# MAIN.net
KiCad netlist of a schematic drawn in Altium Designer
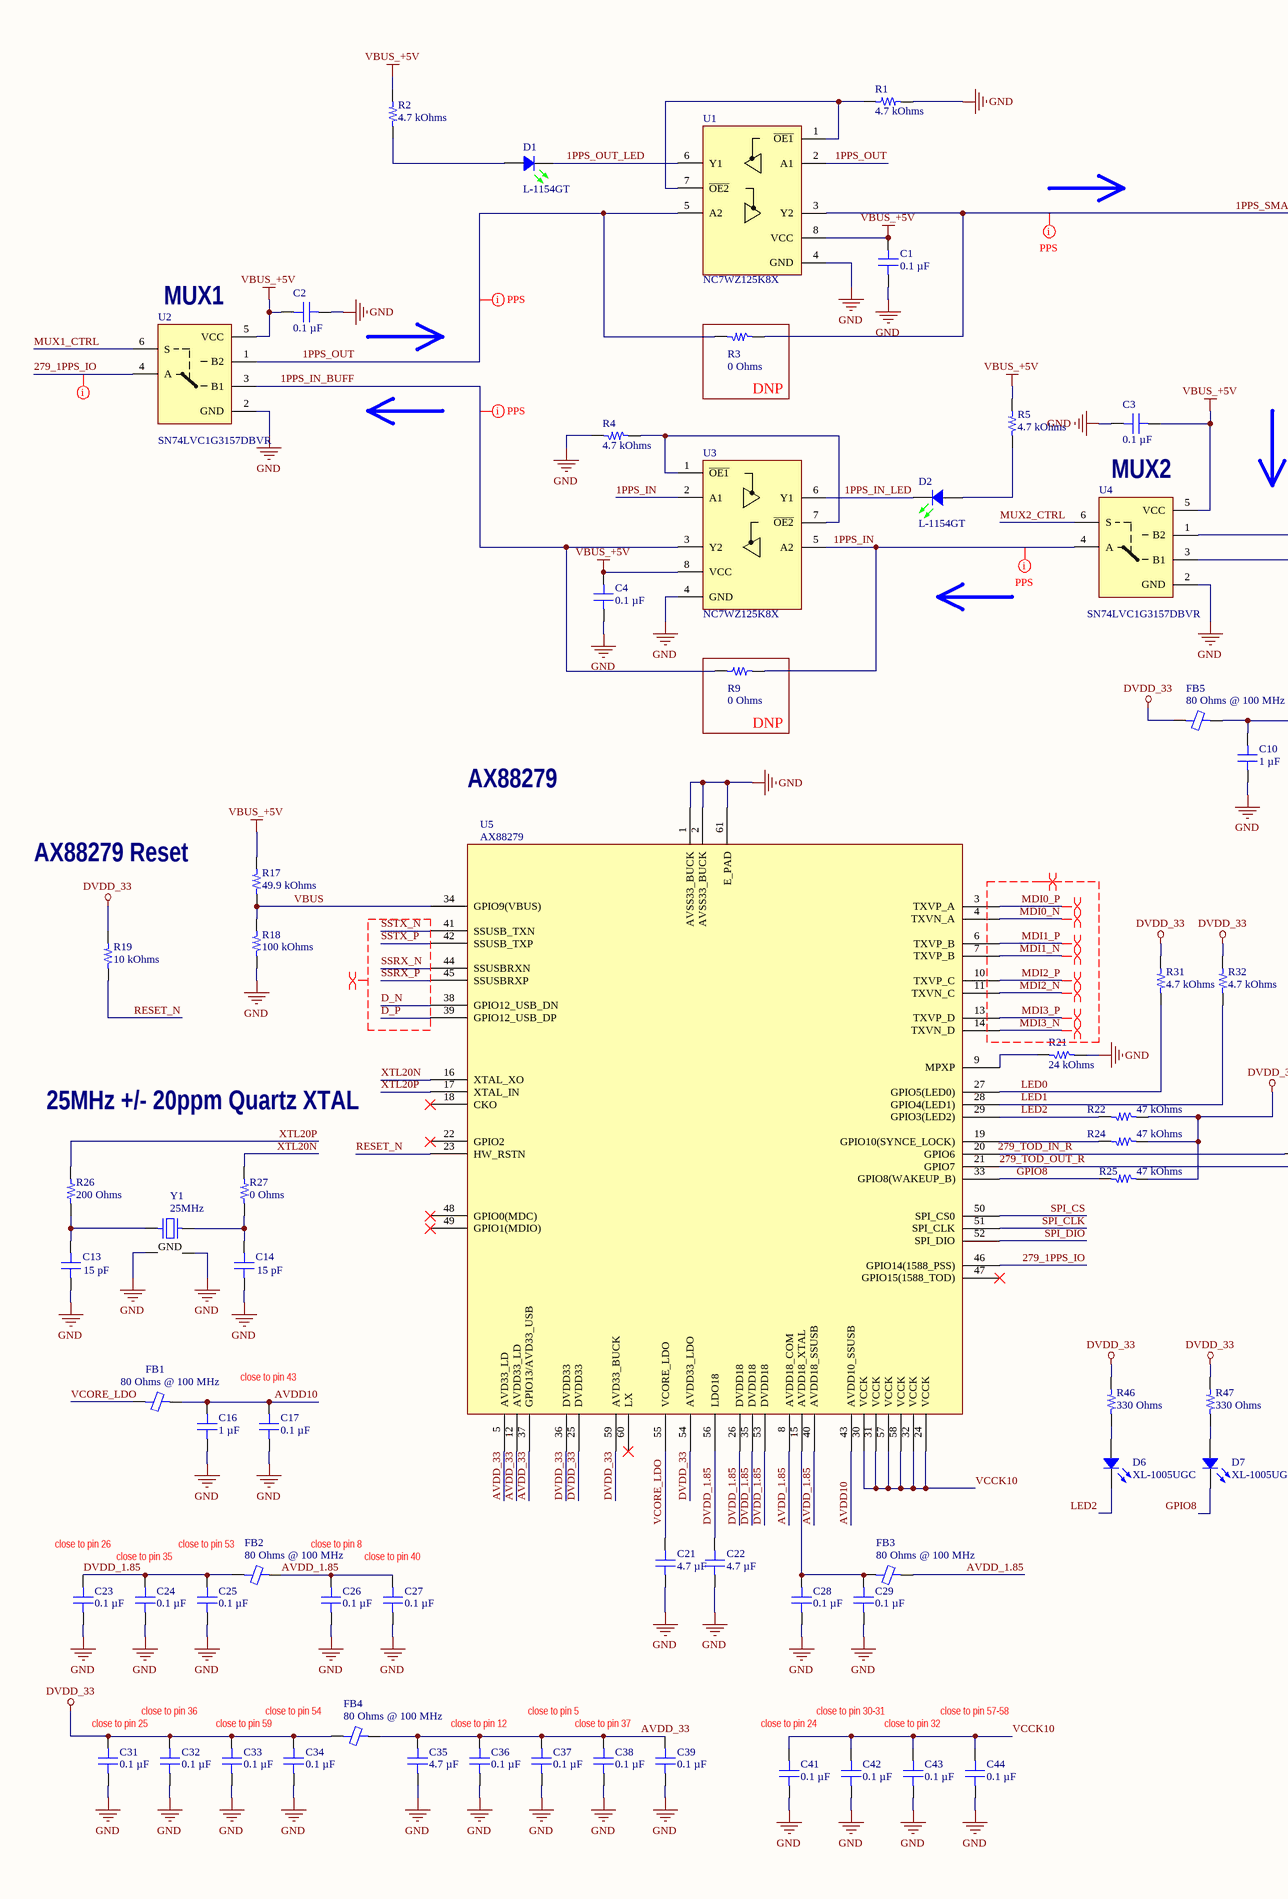
[diagram p0: MAIN.SchDoc, left]
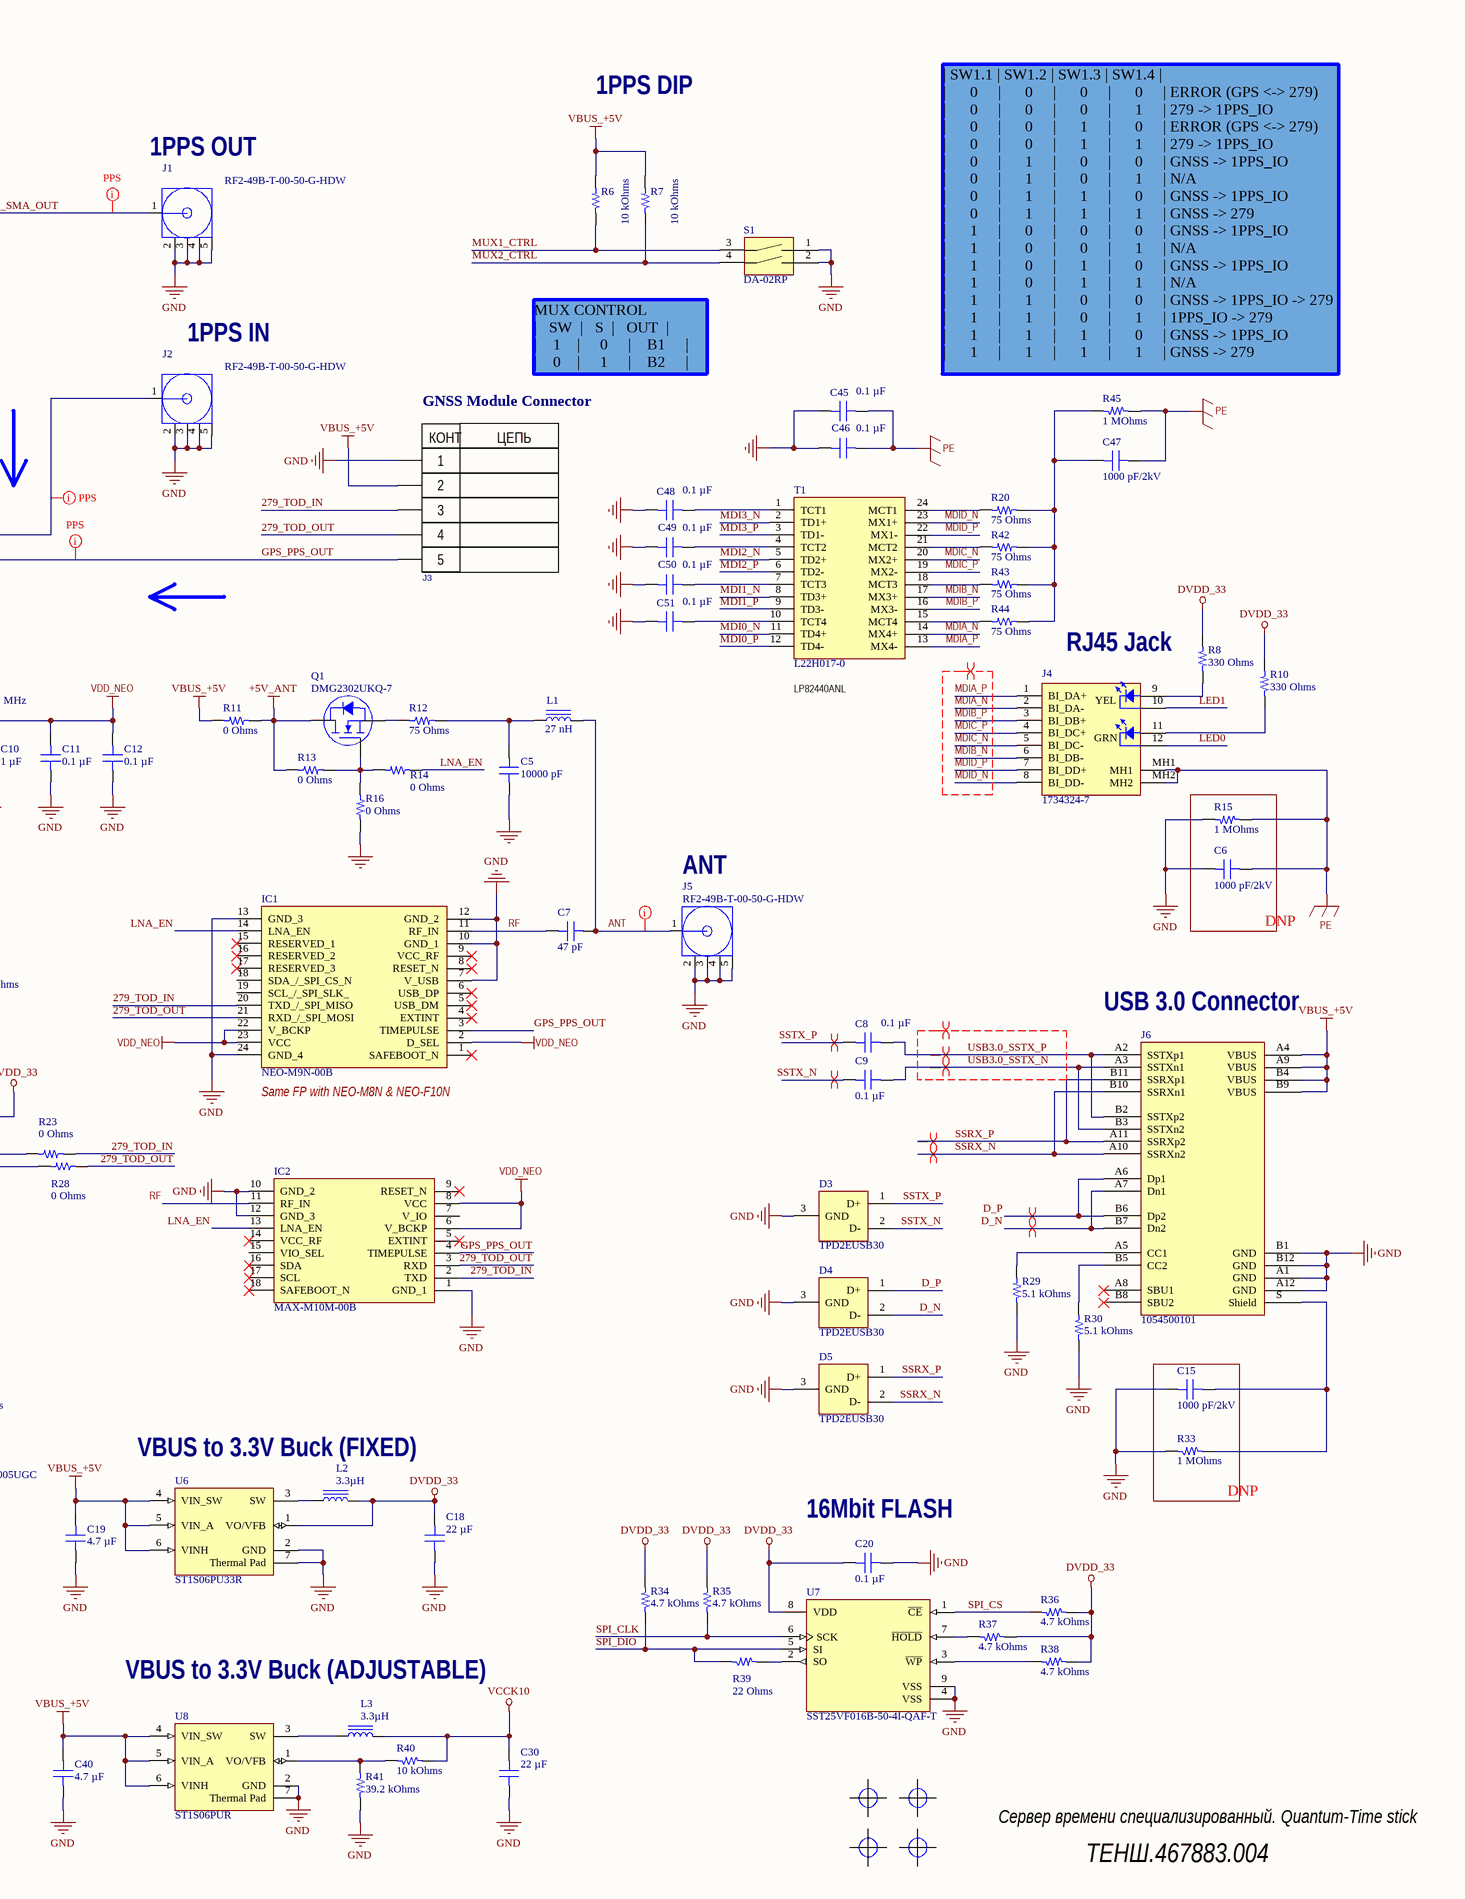
[diagram p1: MAIN.SchDoc, right]

(export (version "E")
  (design (tool "Eeschema 10.0.6"))
  (components
    (comp (ref "C1")
      (value "0.1 µF")
      (footprint "CAP 0402_1005")
      (description "CAP CER 0.1UF 10V X7R 0402")
      (fields (field (name "TOLERANCE") "±10%") (field (name "MANUFACTURER") "Yageo"))
      (libsource (lib "Celestial Altium Library - altium_library") (part "Capacitor"))
    )
    (comp (ref "C2")
      (value "0.1 µF")
      (footprint "CAP 0402_1005")
      (description "CAP CER 0.1UF 10V X7R 0402")
      (fields (field (name "TOLERANCE") "±10%") (field (name "MANUFACTURER") "Yageo"))
      (libsource (lib "Celestial Altium Library - altium_library") (part "Capacitor"))
    )
    (comp (ref "C3")
      (value "0.1 µF")
      (footprint "CAP 0402_1005")
      (description "CAP CER 0.1UF 10V X7R 0402")
      (fields (field (name "TOLERANCE") "±10%") (field (name "MANUFACTURER") "Yageo"))
      (libsource (lib "Celestial Altium Library - altium_library") (part "Capacitor"))
    )
    (comp (ref "C4")
      (value "0.1 µF")
      (footprint "CAP 0402_1005")
      (description "CAP CER 0.1UF 10V X7R 0402")
      (fields (field (name "TOLERANCE") "±10%") (field (name "MANUFACTURER") "Yageo"))
      (libsource (lib "Celestial Altium Library - altium_library") (part "Capacitor"))
    )
    (comp (ref "C5")
      (value "10000 pF")
      (footprint "CAP 0402_1005")
      (description "CAP CER 10000PF 50V X7R 0402")
      (fields (field (name "PART NUMBER") "CC0402KRX7R9BB103") (field (name "MANUFACTURER") "Yageo"))
      (libsource (lib "Celestial Altium Library - altium_library") (part "Capacitor"))
    )
    (comp (ref "C6")
      (value "1000 pF/2kV")
      (footprint "CAP 1206_3216 - 0.8MM")
      (description "CAP CER 1000PF 2KV X7R 1206")
      (fields (field (name "PART NUMBER") "CC1206KKX7RDBB102") (field (name "MANUFACTURER") "Yageo"))
      (libsource (lib "Celestial Altium Library - altium_library") (part "Capacitor"))
    )
    (comp (ref "C7")
      (value "47 pF")
      (footprint "CAP 0402_1005")
      (description "CAP CER 47PF 50V C0G/NPO 0402")
      (fields (field (name "MANUFACTURER") "Yageo") (field (name "TOLERANCE") "±10%"))
      (libsource (lib "Celestial Altium Library - altium_library") (part "Capacitor"))
    )
    (comp (ref "C8")
      (value "0.1 µF")
      (footprint "CAP 0402_1005")
      (description "CAP CER 0.1UF 10V X7R 0402")
      (fields (field (name "TOLERANCE") "±10%") (field (name "MANUFACTURER") "Yageo"))
      (libsource (lib "Celestial Altium Library - altium_library") (part "Capacitor"))
    )
    (comp (ref "C9")
      (value "0.1 µF")
      (footprint "CAP 0402_1005")
      (description "CAP CER 0.1UF 10V X7R 0402")
      (fields (field (name "TOLERANCE") "±10%") (field (name "MANUFACTURER") "Yageo"))
      (libsource (lib "Celestial Altium Library - altium_library") (part "Capacitor"))
    )
    (comp (ref "C10")
      (value "1 µF")
      (footprint "CAP 0402_1005")
      (description "CAP CER 1UF 10V X5R 0402")
      (fields (field (name "TOLERANCE") "±10%") (field (name "MANUFACTURER") "Yageo"))
      (libsource (lib "Celestial Altium Library - altium_library") (part "Capacitor"))
    )
    (comp (ref "C11")
      (value "0.1 µF")
      (footprint "CAP 0402_1005")
      (description "CAP CER 0.1UF 10V X7R 0402")
      (fields (field (name "TOLERANCE") "±10%") (field (name "MANUFACTURER") "Yageo"))
      (libsource (lib "Celestial Altium Library - altium_library") (part "Capacitor"))
    )
    (comp (ref "C12")
      (value "0.1 µF")
      (footprint "CAP 0402_1005")
      (description "CAP CER 0.1UF 10V X7R 0402")
      (fields (field (name "TOLERANCE") "±10%") (field (name "MANUFACTURER") "Yageo"))
      (libsource (lib "Celestial Altium Library - altium_library") (part "Capacitor"))
    )
    (comp (ref "C13")
      (value "15 pF")
      (footprint "CAP 0402_1005")
      (description "CAP CER 15PF 50V C0G/NPO 0402")
      (fields (field (name "MANUFACTURER") "Yageo") (field (name "TOLERANCE") "±10%"))
      (libsource (lib "Celestial Altium Library - altium_library") (part "Capacitor"))
    )
    (comp (ref "C14")
      (value "15 pF")
      (footprint "CAP 0402_1005")
      (description "CAP CER 15PF 50V C0G/NPO 0402")
      (fields (field (name "MANUFACTURER") "Yageo") (field (name "TOLERANCE") "±10%"))
      (libsource (lib "Celestial Altium Library - altium_library") (part "Capacitor"))
    )
    (comp (ref "C15")
      (value "1000 pF/2kV")
      (footprint "CAP 1206_3216 - 0.8MM")
      (description "CAP CER 1000PF 2KV X7R 1206")
      (fields (field (name "PART NUMBER") "CC1206KKX7RDBB102") (field (name "MANUFACTURER") "Yageo"))
      (libsource (lib "Celestial Altium Library - altium_library") (part "Capacitor"))
    )
    (comp (ref "C16")
      (value "1 µF")
      (footprint "CAP 0402_1005")
      (description "CAP CER 1UF 10V X5R 0402")
      (fields (field (name "TOLERANCE") "±10%") (field (name "MANUFACTURER") "Yageo"))
      (libsource (lib "Celestial Altium Library - altium_library") (part "Capacitor"))
    )
    (comp (ref "C17")
      (value "0.1 µF")
      (footprint "CAP 0402_1005")
      (description "CAP CER 0.1UF 10V X7R 0402")
      (fields (field (name "TOLERANCE") "±10%") (field (name "MANUFACTURER") "Yageo"))
      (libsource (lib "Celestial Altium Library - altium_library") (part "Capacitor"))
    )
    (comp (ref "C18")
      (value "22 µF")
      (footprint "CAP 0603_1608")
      (description "CAP CER 22UF 10V X5R 0603")
      (fields (field (name "MANUFACTURER") "Yageo") (field (name "TOLERANCE") "±20%"))
      (libsource (lib "Celestial Altium Library - altium_library") (part "Capacitor"))
    )
    (comp (ref "C19")
      (value "4.7 µF")
      (footprint "CAP 0402_1005")
      (description "CAP CER 4.7UF 10V X5R 0402")
      (fields (field (name "TOLERANCE") "±20%") (field (name "MANUFACTURER") "Yageo"))
      (libsource (lib "Celestial Altium Library - altium_library") (part "Capacitor"))
    )
    (comp (ref "C20")
      (value "0.1 µF")
      (footprint "CAP 0402_1005")
      (description "CAP CER 0.1UF 10V X7R 0402")
      (fields (field (name "TOLERANCE") "±10%") (field (name "MANUFACTURER") "Yageo"))
      (libsource (lib "Celestial Altium Library - altium_library") (part "Capacitor"))
    )
    (comp (ref "C21")
      (value "4.7 µF")
      (footprint "CAP 0402_1005")
      (description "CAP CER 4.7UF 10V X5R 0402")
      (fields (field (name "TOLERANCE") "±20%") (field (name "MANUFACTURER") "Yageo"))
      (libsource (lib "Celestial Altium Library - altium_library") (part "Capacitor"))
    )
    (comp (ref "C22")
      (value "4.7 µF")
      (footprint "CAP 0402_1005")
      (description "CAP CER 4.7UF 10V X5R 0402")
      (fields (field (name "TOLERANCE") "±20%") (field (name "MANUFACTURER") "Yageo"))
      (libsource (lib "Celestial Altium Library - altium_library") (part "Capacitor"))
    )
    (comp (ref "C23")
      (value "0.1 µF")
      (footprint "CAP 0402_1005")
      (description "CAP CER 0.1UF 10V X7R 0402")
      (fields (field (name "TOLERANCE") "±10%") (field (name "MANUFACTURER") "Yageo"))
      (libsource (lib "Celestial Altium Library - altium_library") (part "Capacitor"))
    )
    (comp (ref "C24")
      (value "0.1 µF")
      (footprint "CAP 0402_1005")
      (description "CAP CER 0.1UF 10V X7R 0402")
      (fields (field (name "TOLERANCE") "±10%") (field (name "MANUFACTURER") "Yageo"))
      (libsource (lib "Celestial Altium Library - altium_library") (part "Capacitor"))
    )
    (comp (ref "C25")
      (value "0.1 µF")
      (footprint "CAP 0402_1005")
      (description "CAP CER 0.1UF 10V X7R 0402")
      (fields (field (name "TOLERANCE") "±10%") (field (name "MANUFACTURER") "Yageo"))
      (libsource (lib "Celestial Altium Library - altium_library") (part "Capacitor"))
    )
    (comp (ref "C26")
      (value "0.1 µF")
      (footprint "CAP 0402_1005")
      (description "CAP CER 0.1UF 10V X7R 0402")
      (fields (field (name "TOLERANCE") "±10%") (field (name "MANUFACTURER") "Yageo"))
      (libsource (lib "Celestial Altium Library - altium_library") (part "Capacitor"))
    )
    (comp (ref "C27")
      (value "0.1 µF")
      (footprint "CAP 0402_1005")
      (description "CAP CER 0.1UF 10V X7R 0402")
      (fields (field (name "TOLERANCE") "±10%") (field (name "MANUFACTURER") "Yageo"))
      (libsource (lib "Celestial Altium Library - altium_library") (part "Capacitor"))
    )
    (comp (ref "C28")
      (value "0.1 µF")
      (footprint "CAP 0402_1005")
      (description "CAP CER 0.1UF 10V X7R 0402")
      (fields (field (name "TOLERANCE") "±10%") (field (name "MANUFACTURER") "Yageo"))
      (libsource (lib "Celestial Altium Library - altium_library") (part "Capacitor"))
    )
    (comp (ref "C29")
      (value "0.1 µF")
      (footprint "CAP 0402_1005")
      (description "CAP CER 0.1UF 10V X7R 0402")
      (fields (field (name "TOLERANCE") "±10%") (field (name "MANUFACTURER") "Yageo"))
      (libsource (lib "Celestial Altium Library - altium_library") (part "Capacitor"))
    )
    (comp (ref "C30")
      (value "22 µF")
      (footprint "CAP 0603_1608")
      (description "CAP CER 22UF 10V X5R 0603")
      (fields (field (name "MANUFACTURER") "Yageo") (field (name "TOLERANCE") "±20%"))
      (libsource (lib "Celestial Altium Library - altium_library") (part "Capacitor"))
    )
    (comp (ref "C31")
      (value "0.1 µF")
      (footprint "CAP 0402_1005")
      (description "CAP CER 0.1UF 10V X7R 0402")
      (fields (field (name "TOLERANCE") "±10%") (field (name "MANUFACTURER") "Yageo"))
      (libsource (lib "Celestial Altium Library - altium_library") (part "Capacitor"))
    )
    (comp (ref "C32")
      (value "0.1 µF")
      (footprint "CAP 0402_1005")
      (description "CAP CER 0.1UF 10V X7R 0402")
      (fields (field (name "TOLERANCE") "±10%") (field (name "MANUFACTURER") "Yageo"))
      (libsource (lib "Celestial Altium Library - altium_library") (part "Capacitor"))
    )
    (comp (ref "C33")
      (value "0.1 µF")
      (footprint "CAP 0402_1005")
      (description "CAP CER 0.1UF 10V X7R 0402")
      (fields (field (name "TOLERANCE") "±10%") (field (name "MANUFACTURER") "Yageo"))
      (libsource (lib "Celestial Altium Library - altium_library") (part "Capacitor"))
    )
    (comp (ref "C34")
      (value "0.1 µF")
      (footprint "CAP 0402_1005")
      (description "CAP CER 0.1UF 10V X7R 0402")
      (fields (field (name "TOLERANCE") "±10%") (field (name "MANUFACTURER") "Yageo"))
      (libsource (lib "Celestial Altium Library - altium_library") (part "Capacitor"))
    )
    (comp (ref "C35")
      (value "4.7 µF")
      (footprint "CAP 0402_1005")
      (description "CAP CER 4.7UF 10V X5R 0402")
      (fields (field (name "TOLERANCE") "±20%") (field (name "MANUFACTURER") "Yageo"))
      (libsource (lib "Celestial Altium Library - altium_library") (part "Capacitor"))
    )
    (comp (ref "C36")
      (value "0.1 µF")
      (footprint "CAP 0402_1005")
      (description "CAP CER 0.1UF 10V X7R 0402")
      (fields (field (name "TOLERANCE") "±10%") (field (name "MANUFACTURER") "Yageo"))
      (libsource (lib "Celestial Altium Library - altium_library") (part "Capacitor"))
    )
    (comp (ref "C37")
      (value "0.1 µF")
      (footprint "CAP 0402_1005")
      (description "CAP CER 0.1UF 10V X7R 0402")
      (fields (field (name "TOLERANCE") "±10%") (field (name "MANUFACTURER") "Yageo"))
      (libsource (lib "Celestial Altium Library - altium_library") (part "Capacitor"))
    )
    (comp (ref "C38")
      (value "0.1 µF")
      (footprint "CAP 0402_1005")
      (description "CAP CER 0.1UF 10V X7R 0402")
      (fields (field (name "TOLERANCE") "±10%") (field (name "MANUFACTURER") "Yageo"))
      (libsource (lib "Celestial Altium Library - altium_library") (part "Capacitor"))
    )
    (comp (ref "C39")
      (value "0.1 µF")
      (footprint "CAP 0402_1005")
      (description "CAP CER 0.1UF 10V X7R 0402")
      (fields (field (name "TOLERANCE") "±10%") (field (name "MANUFACTURER") "Yageo"))
      (libsource (lib "Celestial Altium Library - altium_library") (part "Capacitor"))
    )
    (comp (ref "C40")
      (value "4.7 µF")
      (footprint "CAP 0402_1005")
      (description "CAP CER 4.7UF 10V X5R 0402")
      (fields (field (name "TOLERANCE") "±20%") (field (name "MANUFACTURER") "Yageo"))
      (libsource (lib "Celestial Altium Library - altium_library") (part "Capacitor"))
    )
    (comp (ref "C41")
      (value "0.1 µF")
      (footprint "CAP 0402_1005")
      (description "CAP CER 0.1UF 10V X7R 0402")
      (fields (field (name "TOLERANCE") "±10%") (field (name "MANUFACTURER") "Yageo"))
      (libsource (lib "Celestial Altium Library - altium_library") (part "Capacitor"))
    )
    (comp (ref "C42")
      (value "0.1 µF")
      (footprint "CAP 0402_1005")
      (description "CAP CER 0.1UF 10V X7R 0402")
      (fields (field (name "TOLERANCE") "±10%") (field (name "MANUFACTURER") "Yageo"))
      (libsource (lib "Celestial Altium Library - altium_library") (part "Capacitor"))
    )
    (comp (ref "C43")
      (value "0.1 µF")
      (footprint "CAP 0402_1005")
      (description "CAP CER 0.1UF 10V X7R 0402")
      (fields (field (name "TOLERANCE") "±10%") (field (name "MANUFACTURER") "Yageo"))
      (libsource (lib "Celestial Altium Library - altium_library") (part "Capacitor"))
    )
    (comp (ref "C44")
      (value "0.1 µF")
      (footprint "CAP 0402_1005")
      (description "CAP CER 0.1UF 10V X7R 0402")
      (fields (field (name "TOLERANCE") "±10%") (field (name "MANUFACTURER") "Yageo"))
      (libsource (lib "Celestial Altium Library - altium_library") (part "Capacitor"))
    )
    (comp (ref "C45")
      (value "0.1 µF")
      (footprint "CAP 0402_1005")
      (description "CAP CER 0.1UF 10V X7R 0402")
      (fields (field (name "TOLERANCE") "±10%") (field (name "MANUFACTURER") "Yageo"))
      (libsource (lib "Celestial Altium Library - altium_library") (part "Capacitor"))
    )
    (comp (ref "C46")
      (value "0.1 µF")
      (footprint "CAP 0402_1005")
      (description "CAP CER 0.1UF 10V X7R 0402")
      (fields (field (name "TOLERANCE") "±10%") (field (name "MANUFACTURER") "Yageo"))
      (libsource (lib "Celestial Altium Library - altium_library") (part "Capacitor"))
    )
    (comp (ref "C47")
      (value "1000 pF/2kV")
      (footprint "CAP 1206_3216 - 0.8MM")
      (description "CAP CER 1000PF 2KV X7R 1206")
      (fields (field (name "PART NUMBER") "CC1206KKX7RDBB102") (field (name "MANUFACTURER") "Yageo"))
      (libsource (lib "Celestial Altium Library - altium_library") (part "Capacitor"))
    )
    (comp (ref "C48")
      (value "0.1 µF")
      (footprint "CAP 0402_1005")
      (description "CAP CER 0.1UF 10V X7R 0402")
      (fields (field (name "TOLERANCE") "±10%") (field (name "MANUFACTURER") "Yageo"))
      (libsource (lib "Celestial Altium Library - altium_library") (part "Capacitor"))
    )
    (comp (ref "C49")
      (value "0.1 µF")
      (footprint "CAP 0402_1005")
      (description "CAP CER 0.1UF 10V X7R 0402")
      (fields (field (name "TOLERANCE") "±10%") (field (name "MANUFACTURER") "Yageo"))
      (libsource (lib "Celestial Altium Library - altium_library") (part "Capacitor"))
    )
    (comp (ref "C50")
      (value "0.1 µF")
      (footprint "CAP 0402_1005")
      (description "CAP CER 0.1UF 10V X7R 0402")
      (fields (field (name "TOLERANCE") "±10%") (field (name "MANUFACTURER") "Yageo"))
      (libsource (lib "Celestial Altium Library - altium_library") (part "Capacitor"))
    )
    (comp (ref "C51")
      (value "0.1 µF")
      (footprint "CAP 0402_1005")
      (description "CAP CER 0.1UF 10V X7R 0402")
      (fields (field (name "TOLERANCE") "±10%") (field (name "MANUFACTURER") "Yageo"))
      (libsource (lib "Celestial Altium Library - altium_library") (part "Capacitor"))
    )
    (comp (ref "D1")
      (value "L-1154GT")
      (footprint "SamacSys:LED_3MM_GREEN")
      (description "LED, 3mm, Green")
      (libsource (lib "SamacSys") (part "L-1154GT"))
    )
    (comp (ref "D2")
      (value "L-1154GT")
      (footprint "SamacSys:LED_3MM_GREEN")
      (description "LED, 3mm, Green")
      (libsource (lib "SamacSys") (part "L-1154GT"))
    )
    (comp (ref "D3")
      (value "TPD2EUSB30")
      (footprint "SamacSys:SOT35P100X50-3N")
      (description "TVS DIODE 3.6VWM 8VC SOT3")
      (fields
        (field (name "MANUFACTURER_PART_NUMBER") "TPD2EUSB30ADRTR")
        (field (name "MOUSER PART NUMBER") "595-TPD2EUSB30ADRTR")
      )
      (libsource (lib "SamacSys") (part "TPD2EUSB30ADRTR"))
    )
    (comp (ref "D4")
      (value "TPD2EUSB30")
      (footprint "SamacSys:SOT35P100X50-3N")
      (description "TVS DIODE 3.6VWM 8VC SOT3")
      (fields
        (field (name "MANUFACTURER_PART_NUMBER") "TPD2EUSB30ADRTR")
        (field (name "MOUSER PART NUMBER") "595-TPD2EUSB30ADRTR")
      )
      (libsource (lib "SamacSys") (part "TPD2EUSB30ADRTR"))
    )
    (comp (ref "D5")
      (value "TPD2EUSB30")
      (footprint "SamacSys:SOT35P100X50-3N")
      (description "TVS DIODE 3.6VWM 8VC SOT3")
      (fields
        (field (name "MANUFACTURER_PART_NUMBER") "TPD2EUSB30ADRTR")
        (field (name "MOUSER PART NUMBER") "595-TPD2EUSB30ADRTR")
      )
      (libsource (lib "SamacSys") (part "TPD2EUSB30ADRTR"))
    )
    (comp (ref "D6")
      (value "XL-1005UGC")
      (footprint "LED 0402_1005 GREEN")
      (description "LED GREEN CLEAR CHIP SMD")
      (fields (field (name "PART NUMBER") "APHHS1005ZGC") (field (name "MANUFACTURER") "Kingbright"))
      (libsource (lib "Celestial Altium Library - altium_library") (part "LED"))
    )
    (comp (ref "D7")
      (value "XL-1005UGC")
      (footprint "LED 0402_1005 GREEN")
      (description "LED GREEN CLEAR CHIP SMD")
      (fields (field (name "PART NUMBER") "APHHS1005ZGC") (field (name "MANUFACTURER") "Kingbright"))
      (libsource (lib "Celestial Altium Library - altium_library") (part "LED"))
    )
    (comp (ref "FB1")
      (value "80 Ohms @ 100 MHz")
      (footprint "FER 0402_1005")
      (description "FERRITE BEAD 80 OHM 0402 1LN")
      (fields
        (field (name "MANUFACTURER") "Murata Electronics")
        (field (name "PART NUMBER") "BLM15PD800SN1D")
      )
      (libsource (lib "Celestial Altium Library - altium_library") (part "Ferrite Chip"))
    )
    (comp (ref "FB2")
      (value "80 Ohms @ 100 MHz")
      (footprint "FER 0402_1005")
      (description "FERRITE BEAD 80 OHM 0402 1LN")
      (fields
        (field (name "MANUFACTURER") "Murata Electronics")
        (field (name "PART NUMBER") "BLM15PD800SN1D")
      )
      (libsource (lib "Celestial Altium Library - altium_library") (part "Ferrite Chip"))
    )
    (comp (ref "FB3")
      (value "80 Ohms @ 100 MHz")
      (footprint "FER 0402_1005")
      (description "FERRITE BEAD 80 OHM 0402 1LN")
      (fields
        (field (name "MANUFACTURER") "Murata Electronics")
        (field (name "PART NUMBER") "BLM15PD800SN1D")
      )
      (libsource (lib "Celestial Altium Library - altium_library") (part "Ferrite Chip"))
    )
    (comp (ref "FB4")
      (value "80 Ohms @ 100 MHz")
      (footprint "FER 0402_1005")
      (description "FERRITE BEAD 80 OHM 0402 1LN")
      (fields
        (field (name "MANUFACTURER") "Murata Electronics")
        (field (name "PART NUMBER") "BLM15PD800SN1D")
      )
      (libsource (lib "Celestial Altium Library - altium_library") (part "Ferrite Chip"))
    )
    (comp (ref "FB5")
      (value "80 Ohms @ 100 MHz")
      (footprint "FER 0402_1005")
      (description "FERRITE BEAD 80 OHM 0402 1LN")
      (fields
        (field (name "MANUFACTURER") "Murata Electronics")
        (field (name "PART NUMBER") "BLM15PD800SN1D")
      )
      (libsource (lib "Celestial Altium Library - altium_library") (part "Ferrite Chip"))
    )
    (comp (ref "IC1")
      (value "NEO-M9N-00B")
      (footprint "SamacSys:NEOM9N00B")
      (description "Integrated Circuit")
      (fields (field (name "MOUSER PART NUMBER") "377-NEO-M9N-00B"))
      (libsource (lib "SamacSys") (part "NEO-M9N-00B"))
    )
    (comp (ref "IC2")
      (value "MAX-M10M-00B")
      (footprint "MAXM10M00B")
      (description "Integrated Circuit")
      (fields (field (name "MOUSER PART NUMBER") "377-MAX-M10M-00B"))
      (libsource (lib "SamacSys") (part "MAX-M10M-00B"))
    )
    (comp (ref "J1")
      (value "RF2-49B-T-00-50-G-HDW")
      (footprint "SamacSys:RF249BT0050GHDW")
      (description "Connector")
      (libsource (lib "SamacSys") (part "RF2-49B-T-00-50-G-HDW"))
    )
    (comp (ref "J2")
      (value "RF2-49B-T-00-50-G-HDW")
      (footprint "SamacSys:RF249BT0050GHDW")
      (description "Connector")
      (libsource (lib "SamacSys") (part "RF2-49B-T-00-50-G-HDW"))
    )
    (comp (ref "J3")
      (value "PBS-5")
      (footprint "SamacSys:PBS-5")
      (description "Connector")
      (fields (field (name "MANUFACTURER") "Connfly") (field (name "PART NUMBER") "PBD-5"))
      (libsource (lib "SamacSys") (part "PBS-5"))
    )
    (comp (ref "J4")
      (value "1734324-7")
      (footprint "SamacSys:17343247")
      (description "Connector, RJ-45, with LED, w/o Mag, RA")
      (fields (field (name "MOUSER PART NUMBER") "571-1734324-7"))
      (libsource (lib "SamacSys") (part "1734324-7"))
    )
    (comp (ref "J5")
      (value "RF2-49B-T-00-50-G-HDW")
      (footprint "SamacSys:RF249BT0050GHDW")
      (description "Connector")
      (libsource (lib "SamacSys") (part "RF2-49B-T-00-50-G-HDW"))
    )
    (comp (ref "J6")
      (value "1054500101")
      (footprint "Molex 1054500101")
      (description "CONN RCP USB3.1 TYPEC 24P SMD RA")
      (fields (field (name "MANUFACTURER") "Molex"))
      (libsource (lib "Celestial Altium Library - altium_library") (part "USB 3.0 Type C"))
    )
    (comp (ref "L1")
      (value "27 nH")
      (footprint "Murata LQG15 0402")
      (description "FIXED IND 27NH 350MA 0.46OHM SMD")
      (fields
        (field (name "PART NUMBER") "LQG15HS27NJ02D")
        (field (name "MANUFACTURER") "Murata Electronics")
      )
      (libsource (lib "Celestial Altium Library - altium_library") (part "Inductor"))
    )
    (comp (ref "L2")
      (value "3.3µH")
      (footprint "IND 1008_2520")
      (description "FIXED IND 3.3UH 1.2A 100 MOHM")
      (fields (field (name "TOLERANCE") "±20%") (field (name "MANUFACTURER") "Murata Electronics"))
      (libsource (lib "Celestial Altium Library - altium_library") (part "Inductor"))
    )
    (comp (ref "L3")
      (value "3.3µH")
      (footprint "IND 1008_2520")
      (description "FIXED IND 3.3UH 1.2A 100 MOHM")
      (fields (field (name "TOLERANCE") "±20%") (field (name "MANUFACTURER") "Murata Electronics"))
      (libsource (lib "Celestial Altium Library - altium_library") (part "Inductor"))
    )
    (comp (ref "MNT1")
      (value "MOUNT_HOLE")
      (footprint "SamacSys:MOUNT_3mm")
      (description "Mount hole")
      (libsource (lib "SamacSys") (part "MOUNT_HOLE"))
    )
    (comp (ref "MNT2")
      (value "MOUNT_HOLE")
      (footprint "SamacSys:MOUNT_3mm")
      (description "Mount hole")
      (libsource (lib "SamacSys") (part "MOUNT_HOLE"))
    )
    (comp (ref "MNT3")
      (value "MOUNT_HOLE")
      (footprint "SamacSys:MOUNT_3mm")
      (description "Mount hole")
      (libsource (lib "SamacSys") (part "MOUNT_HOLE"))
    )
    (comp (ref "MNT4")
      (value "MOUNT_HOLE")
      (footprint "SamacSys:MOUNT_3mm")
      (description "Mount hole")
      (libsource (lib "SamacSys") (part "MOUNT_HOLE"))
    )
    (comp (ref "Q1")
      (value "DMG2302UKQ-7")
      (footprint "DIODES SOT-23-3")
      (description "MOSFET BVDSS: 8V-24V SOT23 T&R 3")
      (fields (field (name "MANUFACTURER") "Diodes Incorporated"))
      (libsource (lib "Celestial Altium Library - altium_library") (part "DIODES INC MOSFET N-CH SOT-23-3"))
    )
    (comp (ref "R1")
      (value "4.7 kOhms")
      (footprint "YAGEO RES 0402_1005")
      (description "RES 4.7K OHM 1% 1/16W 0402")
      (fields (field (name "TOLERANCE") "±1%") (field (name "MANUFACTURER") "Yageo"))
      (libsource (lib "Celestial Altium Library - altium_library") (part "Resistor"))
    )
    (comp (ref "R2")
      (value "4.7 kOhms")
      (footprint "YAGEO RES 0402_1005")
      (description "RES 4.7K OHM 1% 1/16W 0402")
      (fields (field (name "TOLERANCE") "±1%") (field (name "MANUFACTURER") "Yageo"))
      (libsource (lib "Celestial Altium Library - altium_library") (part "Resistor"))
    )
    (comp (ref "R3")
      (value "0 Ohms")
      (footprint "YAGEO RES 0402_1005")
      (description "RES 0 OHM JUMPER 1/16W 0402")
      (fields (field (name "TOLERANCE") "Jumper") (field (name "MANUFACTURER") "Yageo"))
      (libsource (lib "Celestial Altium Library - altium_library") (part "Resistor"))
    )
    (comp (ref "R4")
      (value "4.7 kOhms")
      (footprint "YAGEO RES 0402_1005")
      (description "RES 4.7K OHM 1% 1/16W 0402")
      (fields (field (name "TOLERANCE") "±1%") (field (name "MANUFACTURER") "Yageo"))
      (libsource (lib "Celestial Altium Library - altium_library") (part "Resistor"))
    )
    (comp (ref "R5")
      (value "4.7 kOhms")
      (footprint "YAGEO RES 0402_1005")
      (description "RES 4.7K OHM 1% 1/16W 0402")
      (fields (field (name "TOLERANCE") "±1%") (field (name "MANUFACTURER") "Yageo"))
      (libsource (lib "Celestial Altium Library - altium_library") (part "Resistor"))
    )
    (comp (ref "R6")
      (value "10 kOhms")
      (footprint "YAGEO RES 0402_1005")
      (description "RES 10K OHM 1% 1/16W 0402")
      (fields (field (name "TOLERANCE") "±1%") (field (name "MANUFACTURER") "Yageo"))
      (libsource (lib "Celestial Altium Library - altium_library") (part "Resistor"))
    )
    (comp (ref "R7")
      (value "10 kOhms")
      (footprint "YAGEO RES 0402_1005")
      (description "RES 10K OHM 1% 1/16W 0402")
      (fields (field (name "TOLERANCE") "±1%") (field (name "MANUFACTURER") "Yageo"))
      (libsource (lib "Celestial Altium Library - altium_library") (part "Resistor"))
    )
    (comp (ref "R8")
      (value "330 Ohms")
      (footprint "YAGEO RES 0402_1005")
      (description "RES 330 OHM 1% 1/16W 0402")
      (fields (field (name "TOLERANCE") "±1%") (field (name "MANUFACTURER") "Yageo"))
      (libsource (lib "Celestial Altium Library - altium_library") (part "Resistor"))
    )
    (comp (ref "R9")
      (value "0 Ohms")
      (footprint "YAGEO RES 0402_1005")
      (description "RES 0 OHM JUMPER 1/16W 0402")
      (fields (field (name "TOLERANCE") "Jumper") (field (name "MANUFACTURER") "Yageo"))
      (libsource (lib "Celestial Altium Library - altium_library") (part "Resistor"))
    )
    (comp (ref "R10")
      (value "330 Ohms")
      (footprint "YAGEO RES 0402_1005")
      (description "RES 330 OHM 1% 1/16W 0402")
      (fields (field (name "TOLERANCE") "±1%") (field (name "MANUFACTURER") "Yageo"))
      (libsource (lib "Celestial Altium Library - altium_library") (part "Resistor"))
    )
    (comp (ref "R11")
      (value "0 Ohms")
      (footprint "YAGEO RES 0402_1005")
      (description "RES 0 OHM JUMPER 1/16W 0402")
      (fields (field (name "TOLERANCE") "Jumper") (field (name "MANUFACTURER") "Yageo"))
      (libsource (lib "Celestial Altium Library - altium_library") (part "Resistor"))
    )
    (comp (ref "R12")
      (value "75 Ohms")
      (footprint "YAGEO RES 0603_1608")
      (description "RES 75 OHM 1% 1/10W 0603")
      (fields (field (name "PART NUMBER") "RC0603FR-0775RL") (field (name "MANUFACTURER") "Yageo"))
      (libsource (lib "Celestial Altium Library - altium_library") (part "Resistor"))
    )
    (comp (ref "R13")
      (value "0 Ohms")
      (footprint "YAGEO RES 0402_1005")
      (description "RES 0 OHM JUMPER 1/16W 0402")
      (fields (field (name "TOLERANCE") "Jumper") (field (name "MANUFACTURER") "Yageo"))
      (libsource (lib "Celestial Altium Library - altium_library") (part "Resistor"))
    )
    (comp (ref "R14")
      (value "0 Ohms")
      (footprint "YAGEO RES 0402_1005")
      (description "RES 0 OHM JUMPER 1/16W 0402")
      (fields (field (name "TOLERANCE") "Jumper") (field (name "MANUFACTURER") "Yageo"))
      (libsource (lib "Celestial Altium Library - altium_library") (part "Resistor"))
    )
    (comp (ref "R15")
      (value "1 MOhms")
      (footprint "YAGEO RES 0402_1005")
      (description "RES 1M OHM 1% 1/16W 0402")
      (fields (field (name "TOLERANCE") "±1%") (field (name "MANUFACTURER") "Yageo"))
      (libsource (lib "Celestial Altium Library - altium_library") (part "Resistor"))
    )
    (comp (ref "R16")
      (value "0 Ohms")
      (footprint "YAGEO RES 0402_1005")
      (description "RES 0 OHM JUMPER 1/16W 0402")
      (fields (field (name "TOLERANCE") "Jumper") (field (name "MANUFACTURER") "Yageo"))
      (libsource (lib "Celestial Altium Library - altium_library") (part "Resistor"))
    )
    (comp (ref "R17")
      (value "49.9 kOhms")
      (footprint "YAGEO RES 0402_1005")
      (description "RES 49.9K OHM 1% 1/16W 0402")
      (fields (field (name "TOLERANCE") "±1%") (field (name "MANUFACTURER") "Yageo"))
      (libsource (lib "Celestial Altium Library - altium_library") (part "Resistor"))
    )
    (comp (ref "R18")
      (value "100 kOhms")
      (footprint "YAGEO RES 0402_1005")
      (description "RES 100K OHM 1% 1/16W 0402")
      (fields (field (name "TOLERANCE") "±1%") (field (name "MANUFACTURER") "Yageo"))
      (libsource (lib "Celestial Altium Library - altium_library") (part "Resistor"))
    )
    (comp (ref "R19")
      (value "10 kOhms")
      (footprint "YAGEO RES 0402_1005")
      (description "RES 10K OHM 1% 1/16W 0402")
      (fields (field (name "TOLERANCE") "±1%") (field (name "MANUFACTURER") "Yageo"))
      (libsource (lib "Celestial Altium Library - altium_library") (part "Resistor"))
    )
    (comp (ref "R20")
      (value "75 Ohms")
      (footprint "YAGEO RES 0603_1608")
      (description "RES 75 OHM 1% 1/10W 0603")
      (fields (field (name "PART NUMBER") "RC0603FR-0775RL") (field (name "MANUFACTURER") "Yageo"))
      (libsource (lib "Celestial Altium Library - altium_library") (part "Resistor"))
    )
    (comp (ref "R21")
      (value "24 kOhms")
      (footprint "YAGEO RES 0402_1005")
      (description "RES 24K OHM 1% 1/16W 0402")
      (fields (field (name "TOLERANCE") "±1%") (field (name "MANUFACTURER") "Yageo"))
      (libsource (lib "Celestial Altium Library - altium_library") (part "Resistor"))
    )
    (comp (ref "R22")
      (value "47 kOhms")
      (footprint "YAGEO RES 0402_1005")
      (description "RES 47K OHM 1% 1/16W 0402")
      (fields (field (name "TOLERANCE") "±1%") (field (name "MANUFACTURER") "Yageo"))
      (libsource (lib "Celestial Altium Library - altium_library") (part "Resistor"))
    )
    (comp (ref "R23")
      (value "0 Ohms")
      (footprint "YAGEO RES 0402_1005")
      (description "RES 0 OHM JUMPER 1/16W 0402")
      (fields (field (name "TOLERANCE") "Jumper") (field (name "MANUFACTURER") "Yageo"))
      (libsource (lib "Celestial Altium Library - altium_library") (part "Resistor"))
    )
    (comp (ref "R24")
      (value "47 kOhms")
      (footprint "YAGEO RES 0402_1005")
      (description "RES 47K OHM 1% 1/16W 0402")
      (fields (field (name "TOLERANCE") "±1%") (field (name "MANUFACTURER") "Yageo"))
      (libsource (lib "Celestial Altium Library - altium_library") (part "Resistor"))
    )
    (comp (ref "R25")
      (value "47 kOhms")
      (footprint "YAGEO RES 0402_1005")
      (description "RES 47K OHM 1% 1/16W 0402")
      (fields (field (name "TOLERANCE") "±1%") (field (name "MANUFACTURER") "Yageo"))
      (libsource (lib "Celestial Altium Library - altium_library") (part "Resistor"))
    )
    (comp (ref "R26")
      (value "200 Ohms")
      (footprint "YAGEO RES 0402_1005")
      (description "RES 200 OHM 1% 1/16W 0402")
      (fields (field (name "TOLERANCE") "±1%") (field (name "MANUFACTURER") "Yageo"))
      (libsource (lib "Celestial Altium Library - altium_library") (part "Resistor"))
    )
    (comp (ref "R27")
      (value "0 Ohms")
      (footprint "YAGEO RES 0402_1005")
      (description "RES 0 OHM JUMPER 1/16W 0402")
      (fields (field (name "MANUFACTURER") "Yageo") (field (name "PART NUMBER") "RC0402FR-070RL"))
      (libsource (lib "Celestial Altium Library - altium_library") (part "Resistor"))
    )
    (comp (ref "R28")
      (value "0 Ohms")
      (footprint "YAGEO RES 0402_1005")
      (description "RES 0 OHM JUMPER 1/16W 0402")
      (fields (field (name "TOLERANCE") "Jumper") (field (name "MANUFACTURER") "Yageo"))
      (libsource (lib "Celestial Altium Library - altium_library") (part "Resistor"))
    )
    (comp (ref "R29")
      (value "5.1 kOhms")
      (footprint "YAGEO RES 0402_1005")
      (description "RES 5.1K OHM 1% 1/16W 0402")
      (fields (field (name "TOLERANCE") "±1%") (field (name "MANUFACTURER") "Yageo"))
      (libsource (lib "Celestial Altium Library - altium_library") (part "Resistor"))
    )
    (comp (ref "R30")
      (value "5.1 kOhms")
      (footprint "YAGEO RES 0402_1005")
      (description "RES 5.1K OHM 1% 1/16W 0402")
      (fields (field (name "TOLERANCE") "±1%") (field (name "MANUFACTURER") "Yageo"))
      (libsource (lib "Celestial Altium Library - altium_library") (part "Resistor"))
    )
    (comp (ref "R31")
      (value "4.7 kOhms")
      (footprint "YAGEO RES 0402_1005")
      (description "RES 4.7K OHM 1% 1/16W 0402")
      (fields (field (name "TOLERANCE") "±1%") (field (name "MANUFACTURER") "Yageo"))
      (libsource (lib "Celestial Altium Library - altium_library") (part "Resistor"))
    )
    (comp (ref "R32")
      (value "4.7 kOhms")
      (footprint "YAGEO RES 0402_1005")
      (description "RES 4.7K OHM 1% 1/16W 0402")
      (fields (field (name "TOLERANCE") "±1%") (field (name "MANUFACTURER") "Yageo"))
      (libsource (lib "Celestial Altium Library - altium_library") (part "Resistor"))
    )
    (comp (ref "R33")
      (value "1 MOhms")
      (footprint "YAGEO RES 0402_1005")
      (description "RES 1M OHM 1% 1/16W 0402")
      (fields (field (name "TOLERANCE") "±1%") (field (name "MANUFACTURER") "Yageo"))
      (libsource (lib "Celestial Altium Library - altium_library") (part "Resistor"))
    )
    (comp (ref "R34")
      (value "4.7 kOhms")
      (footprint "YAGEO RES 0402_1005")
      (description "RES 4.7K OHM 1% 1/16W 0402")
      (fields (field (name "TOLERANCE") "±1%") (field (name "MANUFACTURER") "Yageo"))
      (libsource (lib "Celestial Altium Library - altium_library") (part "Resistor"))
    )
    (comp (ref "R35")
      (value "4.7 kOhms")
      (footprint "YAGEO RES 0402_1005")
      (description "RES 4.7K OHM 1% 1/16W 0402")
      (fields (field (name "TOLERANCE") "±1%") (field (name "MANUFACTURER") "Yageo"))
      (libsource (lib "Celestial Altium Library - altium_library") (part "Resistor"))
    )
    (comp (ref "R36")
      (value "4.7 kOhms")
      (footprint "YAGEO RES 0402_1005")
      (description "RES 4.7K OHM 1% 1/16W 0402")
      (fields (field (name "TOLERANCE") "±1%") (field (name "MANUFACTURER") "Yageo"))
      (libsource (lib "Celestial Altium Library - altium_library") (part "Resistor"))
    )
    (comp (ref "R37")
      (value "4.7 kOhms")
      (footprint "YAGEO RES 0402_1005")
      (description "RES 4.7K OHM 1% 1/16W 0402")
      (fields (field (name "TOLERANCE") "±1%") (field (name "MANUFACTURER") "Yageo"))
      (libsource (lib "Celestial Altium Library - altium_library") (part "Resistor"))
    )
    (comp (ref "R38")
      (value "4.7 kOhms")
      (footprint "YAGEO RES 0402_1005")
      (description "RES 4.7K OHM 1% 1/16W 0402")
      (fields (field (name "TOLERANCE") "±1%") (field (name "MANUFACTURER") "Yageo"))
      (libsource (lib "Celestial Altium Library - altium_library") (part "Resistor"))
    )
    (comp (ref "R39")
      (value "22 Ohms")
      (footprint "YAGEO RES 0402_1005")
      (description "RES 22 OHM 1% 1/16W 0402")
      (fields (field (name "TOLERANCE") "±1%") (field (name "MANUFACTURER") "Yageo"))
      (libsource (lib "Celestial Altium Library - altium_library") (part "Resistor"))
    )
    (comp (ref "R40")
      (value "10 kOhms")
      (footprint "YAGEO RES 0402_1005")
      (description "RES 10K OHM 1% 1/16W 0402")
      (fields (field (name "TOLERANCE") "±1%") (field (name "MANUFACTURER") "Yageo"))
      (libsource (lib "Celestial Altium Library - altium_library") (part "Resistor"))
    )
    (comp (ref "R41")
      (value "39.2 kOhms")
      (footprint "YAGEO RES 0402_1005")
      (description "RES 39.2K OHM 1% 1/16W 0402")
      (fields (field (name "TOLERANCE") "±1%") (field (name "MANUFACTURER") "Yageo"))
      (libsource (lib "Celestial Altium Library - altium_library") (part "Resistor"))
    )
    (comp (ref "R42")
      (value "75 Ohms")
      (footprint "YAGEO RES 0603_1608")
      (description "RES 75 OHM 1% 1/10W 0603")
      (fields (field (name "PART NUMBER") "RC0603FR-0775RL") (field (name "MANUFACTURER") "Yageo"))
      (libsource (lib "Celestial Altium Library - altium_library") (part "Resistor"))
    )
    (comp (ref "R43")
      (value "75 Ohms")
      (footprint "YAGEO RES 0603_1608")
      (description "RES 75 OHM 1% 1/10W 0603")
      (fields (field (name "PART NUMBER") "RC0603FR-0775RL") (field (name "MANUFACTURER") "Yageo"))
      (libsource (lib "Celestial Altium Library - altium_library") (part "Resistor"))
    )
    (comp (ref "R44")
      (value "75 Ohms")
      (footprint "YAGEO RES 0603_1608")
      (description "RES 75 OHM 1% 1/10W 0603")
      (fields (field (name "PART NUMBER") "RC0603FR-0775RL") (field (name "MANUFACTURER") "Yageo"))
      (libsource (lib "Celestial Altium Library - altium_library") (part "Resistor"))
    )
    (comp (ref "R45")
      (value "1 MOhms")
      (footprint "YAGEO RES 0402_1005")
      (description "RES 1M OHM 1% 1/16W 0402")
      (fields (field (name "TOLERANCE") "±1%") (field (name "MANUFACTURER") "Yageo"))
      (libsource (lib "Celestial Altium Library - altium_library") (part "Resistor"))
    )
    (comp (ref "R46")
      (value "330 Ohms")
      (footprint "YAGEO RES 0402_1005")
      (description "RES 330 OHM 1% 1/16W 0402")
      (fields (field (name "TOLERANCE") "±1%") (field (name "MANUFACTURER") "Yageo"))
      (libsource (lib "Celestial Altium Library - altium_library") (part "Resistor"))
    )
    (comp (ref "R47")
      (value "330 Ohms")
      (footprint "YAGEO RES 0402_1005")
      (description "RES 330 OHM 1% 1/16W 0402")
      (fields (field (name "TOLERANCE") "±1%") (field (name "MANUFACTURER") "Yageo"))
      (libsource (lib "Celestial Altium Library - altium_library") (part "Resistor"))
    )
    (comp (ref "S1")
      (value "DA-02RP")
      (footprint "SamacSys:DA02RP")
      (description "DIP Switch, 2P")
      (libsource (lib "SamacSys") (part "DA-02RP"))
    )
    (comp (ref "T1")
      (value "L22H017-0")
      (footprint "SamacSys:SOP99P1000X432-24N")
      (description "2.5G BaseT\r\nSingle Port LAN Filter")
      (libsource (lib "SamacSys") (part "L22H017-0"))
    )
    (comp (ref "U1")
      (value "NC7WZ125K8X")
      (footprint "SamacSys:SOP50P310X90-8N")
      (description "Integrated Circuit")
      (libsource (lib "") (part "NC7WZ125K8X_1"))
    )
    (comp (ref "U2")
      (value "SN74LVC1G3157DBVR")
      (footprint "SamacSys:SOT95P280X145-6N")
      (description "Integrated Circuit")
      (fields (field (name "MOUSER PART NUMBER") "595-SN74LVC1G3157DBV"))
      (libsource (lib "SamacSys") (part "SN74LVC1G3157DBVR"))
    )
    (comp (ref "U3")
      (value "NC7WZ125K8X")
      (footprint "SamacSys:SOP50P310X90-8N")
      (description "Integrated Circuit")
      (libsource (lib "SamacSys") (part "NC7WZ125K8X"))
    )
    (comp (ref "U4")
      (value "SN74LVC1G3157DBVR")
      (footprint "SamacSys:SOT95P280X145-6N")
      (description "Integrated Circuit")
      (fields (field (name "MOUSER PART NUMBER") "595-SN74LVC1G3157DBV"))
      (libsource (lib "SamacSys") (part "SN74LVC1G3157DBVR"))
    )
    (comp (ref "U5")
      (value "AX88279")
      (footprint "IC_AX88279")
      (libsource (lib "LotusSound") (part "IC_AX88279"))
    )
    (comp (ref "U6")
      (value "ST1S06PU33R")
      (footprint "DFN6D_L")
      (fields (field (name "MANUFACTURER") "STMicroelectronics"))
      (libsource (lib "Altium Content Vault") (part "PM-DCDC-ST1S06-IL7"))
    )
    (comp (ref "U7")
      (value "SST25VF016B-50-4I-QAF-T")
      (footprint "FP-C04-452-MFG")
      (libsource (lib "Altium Content Vault") (part "d7313dde12fd16fde488169701056cc"))
    )
    (comp (ref "U8")
      (value "ST1S06PUR")
      (footprint "DFN6D_M")
      (libsource (lib "Altium Content Vault") (part "PM-DCDC-ST1S06-IL7"))
    )
    (comp (ref "Y1")
      (value "25MHz")
      (footprint "ABRACON ABM8G")
      (description "CRYSTAL 25.0000MHZ 18PF SMD")
      (fields
        (field (name "MANUFACTURER") "Abracon LLC")
        (field (name "PART NUMBER") "ABM8G-25.000MHZ-18-D2Y-T")
      )
      (libsource (lib "Celestial Altium Library - altium_library") (part "Abracon Crystal ABM8G"))
    )
  )
  (nets
    (net (code "1") (name "+5V_ANT") (class "Default")
      (node (ref "Q1") (pin "3") (pinfunction "D_3") (pintype "passive"))
      (node (ref "R11") (pin "1") (pinfunction "1_1") (pintype "passive"))
      (node (ref "R13") (pin "2") (pinfunction "2_2") (pintype "passive"))
    )
    (net (code "2") (name "/1PPS_IN") (class "Default")
      (node (ref "R9") (pin "1") (pinfunction "1_1") (pintype "passive"))
      (node (ref "U3") (pin "2") (pinfunction "A1_2") (pintype "passive"))
      (node (ref "U3") (pin "5") (pinfunction "A2_5") (pintype "passive"))
      (node (ref "U4") (pin "4") (pinfunction "A_4") (pintype "passive"))
    )
    (net (code "3") (name "/1PPS_IN_BUFF") (class "Default")
      (node (ref "R9") (pin "2") (pinfunction "2_2") (pintype "passive"))
      (node (ref "U2") (pin "3") (pinfunction "B1_3") (pintype "passive"))
      (node (ref "U3") (pin "3") (pinfunction "Y2_3") (pintype "passive"))
    )
    (net (code "4") (name "/1PPS_IN_LED") (class "Default")
      (node (ref "D2") (pin "C") (pinfunction "C_C") (pintype "passive"))
      (node (ref "U3") (pin "6") (pinfunction "Y1_6") (pintype "passive"))
    )
    (net (code "5") (name "/1PPS_OUT") (class "Default")
      (node (ref "R3") (pin "2") (pinfunction "2_2") (pintype "passive"))
      (node (ref "U1") (pin "2") (pinfunction "A1_2") (pintype "passive"))
      (node (ref "U1") (pin "5") (pinfunction "A2_5") (pintype "passive"))
      (node (ref "U2") (pin "1") (pinfunction "B2_1") (pintype "passive"))
    )
    (net (code "6") (name "/1PPS_OUT_LED") (class "Default")
      (node (ref "D1") (pin "C") (pinfunction "C_C") (pintype "passive"))
      (node (ref "U1") (pin "6") (pinfunction "Y1_6") (pintype "passive"))
    )
    (net (code "7") (name "/1PPS_SMA_OUT") (class "Default")
      (node (ref "J1") (pin "1") (pinfunction "1_1") (pintype "passive"))
      (node (ref "R3") (pin "1") (pinfunction "1_1") (pintype "passive"))
      (node (ref "U1") (pin "3") (pinfunction "Y2_3") (pintype "passive"))
    )
    (net (code "8") (name "/279_1PPS_IO") (class "Default")
      (node (ref "U2") (pin "4") (pinfunction "A_4") (pintype "passive"))
      (node (ref "U5") (pin "46") (pinfunction "GPIO14(1588_PSS)_46") (pintype "passive"))
    )
    (net (code "9") (name "/279_TOD_IN") (class "Default")
      (node (ref "IC1") (pin "20") (pinfunction "TXD_/_SPI_MISO_20") (pintype "passive"))
      (node (ref "IC2") (pin "2") (pinfunction "TXD_2") (pintype "passive"))
      (node (ref "J3") (pin "3") (pinfunction "3_3") (pintype "passive"))
      (node (ref "R23") (pin "1") (pinfunction "1_1") (pintype "passive"))
    )
    (net (code "10") (name "/279_TOD_IN_R") (class "Default")
      (node (ref "R23") (pin "2") (pinfunction "2_2") (pintype "passive"))
      (node (ref "U5") (pin "20") (pinfunction "GPIO6_20") (pintype "passive"))
    )
    (net (code "11") (name "/279_TOD_OUT") (class "Default")
      (node (ref "IC1") (pin "21") (pinfunction "RXD_/_SPI_MOSI_21") (pintype "passive"))
      (node (ref "IC2") (pin "3") (pinfunction "RXD_3") (pintype "passive"))
      (node (ref "J3") (pin "4") (pinfunction "4_4") (pintype "passive"))
      (node (ref "R28") (pin "1") (pinfunction "1_1") (pintype "passive"))
    )
    (net (code "12") (name "/279_TOD_OUT_R") (class "Default")
      (node (ref "R28") (pin "2") (pinfunction "2_2") (pintype "passive"))
      (node (ref "U5") (pin "21") (pinfunction "GPIO7_21") (pintype "passive"))
    )
    (net (code "13") (name "/ANT") (class "Default")
      (node (ref "C7") (pin "1") (pinfunction "1_1") (pintype "passive"))
      (node (ref "J5") (pin "1") (pinfunction "1_1") (pintype "passive"))
      (node (ref "L1") (pin "2") (pinfunction "2_2") (pintype "passive"))
    )
    (net (code "14") (name "/AVDD10") (class "Default")
      (node (ref "C16") (pin "2") (pinfunction "2_2") (pintype "passive"))
      (node (ref "C17") (pin "2") (pinfunction "2_2") (pintype "passive"))
      (node (ref "FB1") (pin "2") (pinfunction "2_2") (pintype "passive"))
      (node (ref "U5") (pin "43") (pinfunction "AVDD10_SSUSB_43") (pintype "passive"))
    )
    (net (code "15") (name "/AVDD_1.85") (class "Default")
      (node (ref "C26") (pin "2") (pinfunction "2_2") (pintype "passive"))
      (node (ref "C27") (pin "2") (pinfunction "2_2") (pintype "passive"))
      (node (ref "FB2") (pin "2") (pinfunction "2_2") (pintype "passive"))
      (node (ref "FB3") (pin "2") (pinfunction "2_2") (pintype "passive"))
      (node (ref "U5") (pin "40") (pinfunction "AVDD18_SSUSB_40") (pintype "passive"))
      (node (ref "U5") (pin "8") (pinfunction "AVDD18_COM_8") (pintype "passive"))
    )
    (net (code "16") (name "/AVDD_33") (class "Default")
      (node (ref "C35") (pin "2") (pinfunction "2_2") (pintype "passive"))
      (node (ref "C36") (pin "2") (pinfunction "2_2") (pintype "passive"))
      (node (ref "C37") (pin "2") (pinfunction "2_2") (pintype "passive"))
      (node (ref "C38") (pin "2") (pinfunction "2_2") (pintype "passive"))
      (node (ref "C39") (pin "2") (pinfunction "2_2") (pintype "passive"))
      (node (ref "FB4") (pin "2") (pinfunction "2_2") (pintype "passive"))
      (node (ref "U5") (pin "12") (pinfunction "AVDD33_LD_12") (pintype "passive"))
      (node (ref "U5") (pin "37") (pinfunction "GPIO13/AVD33_USB_37") (pintype "passive"))
      (node (ref "U5") (pin "5") (pinfunction "AVD33_LD_5") (pintype "passive"))
    )
    (net (code "17") (name "/DVDD_1.85") (class "Default")
      (node (ref "C22") (pin "2") (pinfunction "2_2") (pintype "passive"))
      (node (ref "C23") (pin "2") (pinfunction "2_2") (pintype "passive"))
      (node (ref "C24") (pin "2") (pinfunction "2_2") (pintype "passive"))
      (node (ref "C25") (pin "2") (pinfunction "2_2") (pintype "passive"))
      (node (ref "FB2") (pin "1") (pinfunction "1_1") (pintype "passive"))
      (node (ref "U5") (pin "26") (pinfunction "DVDD18_26") (pintype "passive"))
      (node (ref "U5") (pin "35") (pinfunction "DVDD18_35") (pintype "passive"))
      (node (ref "U5") (pin "53") (pinfunction "DVDD18_53") (pintype "passive"))
      (node (ref "U5") (pin "56") (pinfunction "LDO18_56") (pintype "passive"))
    )
    (net (code "18") (name "/D_N") (class "Default")
      (node (ref "D4") (pin "2") (pinfunction "D-_2") (pintype "passive"))
      (node (ref "J6") (pin "A7") (pinfunction "Dn1_A7") (pintype "passive"))
      (node (ref "J6") (pin "B7") (pinfunction "Dn2_B7") (pintype "passive"))
      (node (ref "U5") (pin "38") (pinfunction "GPIO12_USB_DN_38") (pintype "passive"))
    )
    (net (code "19") (name "/D_P") (class "Default")
      (node (ref "D4") (pin "1") (pinfunction "D+_1") (pintype "passive"))
      (node (ref "J6") (pin "A6") (pinfunction "Dp1_A6") (pintype "passive"))
      (node (ref "J6") (pin "B6") (pinfunction "Dp2_B6") (pintype "passive"))
      (node (ref "U5") (pin "39") (pinfunction "GPIO12_USB_DP_39") (pintype "passive"))
    )
    (net (code "20") (name "/GPIO8") (class "Default")
      (node (ref "D7") (pin "2") (pinfunction "2_2") (pintype "passive"))
      (node (ref "R25") (pin "1") (pinfunction "1_1") (pintype "passive"))
      (node (ref "U5") (pin "33") (pinfunction "GPIO8(WAKEUP_B)_33") (pintype "passive"))
    )
    (net (code "21") (name "/GPS_PPS_OUT") (class "Default")
      (node (ref "IC1") (pin "3") (pinfunction "TIMEPULSE_3") (pintype "passive"))
      (node (ref "IC2") (pin "4") (pinfunction "TIMEPULSE_4") (pintype "passive"))
      (node (ref "J3") (pin "5") (pinfunction "5_5") (pintype "passive"))
      (node (ref "U4") (pin "3") (pinfunction "B1_3") (pintype "passive"))
    )
    (net (code "22") (name "/LED0") (class "Default")
      (node (ref "J4") (pin "12") (pinfunction "K_GR_12") (pintype "passive"))
      (node (ref "R31") (pin "2") (pinfunction "2_2") (pintype "passive"))
      (node (ref "U5") (pin "27") (pinfunction "GPIO5(LED0)_27") (pintype "passive"))
    )
    (net (code "23") (name "/LED1") (class "Default")
      (node (ref "J4") (pin "10") (pinfunction "K_YEL_10") (pintype "passive"))
      (node (ref "R32") (pin "2") (pinfunction "2_2") (pintype "passive"))
      (node (ref "U5") (pin "28") (pinfunction "GPIO4(LED1)_28") (pintype "passive"))
    )
    (net (code "24") (name "/LED2") (class "Default")
      (node (ref "D6") (pin "2") (pinfunction "2_2") (pintype "passive"))
      (node (ref "R22") (pin "1") (pinfunction "1_1") (pintype "passive"))
      (node (ref "U5") (pin "29") (pinfunction "GPIO3(LED2)_29") (pintype "passive"))
    )
    (net (code "25") (name "/LNA_EN") (class "Default")
      (node (ref "IC1") (pin "14") (pinfunction "LNA_EN_14") (pintype "passive"))
      (node (ref "IC2") (pin "13") (pinfunction "LNA_EN_13") (pintype "passive"))
      (node (ref "R14") (pin "1") (pinfunction "1_1") (pintype "passive"))
    )
    (net (code "26") (name "/MDI0_N") (class "Default")
      (node (ref "T1") (pin "11") (pinfunction "TD4+_11") (pintype "passive"))
      (node (ref "U5") (pin "4") (pinfunction "TXVN_A_4") (pintype "passive"))
    )
    (net (code "27") (name "/MDI0_P") (class "Default")
      (node (ref "T1") (pin "12") (pinfunction "TD4-_12") (pintype "passive"))
      (node (ref "U5") (pin "3") (pinfunction "TXVP_A_3") (pintype "passive"))
    )
    (net (code "28") (name "/MDI1_N") (class "Default")
      (node (ref "T1") (pin "8") (pinfunction "TD3+_8") (pintype "passive"))
      (node (ref "U5") (pin "7") (pinfunction "TXVP_B_7") (pintype "passive"))
    )
    (net (code "29") (name "/MDI1_P") (class "Default")
      (node (ref "T1") (pin "9") (pinfunction "TD3-_9") (pintype "passive"))
      (node (ref "U5") (pin "6") (pinfunction "TXVP_B_6") (pintype "passive"))
    )
    (net (code "30") (name "/MDI2_N") (class "Default")
      (node (ref "T1") (pin "5") (pinfunction "TD2+_5") (pintype "passive"))
      (node (ref "U5") (pin "11") (pinfunction "TXVN_C_11") (pintype "passive"))
    )
    (net (code "31") (name "/MDI2_P") (class "Default")
      (node (ref "T1") (pin "6") (pinfunction "TD2-_6") (pintype "passive"))
      (node (ref "U5") (pin "10") (pinfunction "TXVP_C_10") (pintype "passive"))
    )
    (net (code "32") (name "/MDI3_N") (class "Default")
      (node (ref "T1") (pin "2") (pinfunction "TD1+_2") (pintype "passive"))
      (node (ref "U5") (pin "14") (pinfunction "TXVN_D_14") (pintype "passive"))
    )
    (net (code "33") (name "/MDI3_P") (class "Default")
      (node (ref "T1") (pin "3") (pinfunction "TD1-_3") (pintype "passive"))
      (node (ref "U5") (pin "13") (pinfunction "TXVP_D_13") (pintype "passive"))
    )
    (net (code "34") (name "/MDIA_N") (class "Default")
      (node (ref "J4") (pin "2") (pinfunction "BI_DA-_2") (pintype "passive"))
      (node (ref "T1") (pin "14") (pinfunction "MX4+_14") (pintype "passive"))
    )
    (net (code "35") (name "/MDIA_P") (class "Default")
      (node (ref "J4") (pin "1") (pinfunction "BI_DA+_1") (pintype "passive"))
      (node (ref "T1") (pin "13") (pinfunction "MX4-_13") (pintype "passive"))
    )
    (net (code "36") (name "/MDIB_N") (class "Default")
      (node (ref "J4") (pin "6") (pinfunction "BI_DB-_6") (pintype "passive"))
      (node (ref "T1") (pin "17") (pinfunction "MX3+_17") (pintype "passive"))
    )
    (net (code "37") (name "/MDIB_P") (class "Default")
      (node (ref "J4") (pin "3") (pinfunction "BI_DB+_3") (pintype "passive"))
      (node (ref "T1") (pin "16") (pinfunction "MX3-_16") (pintype "passive"))
    )
    (net (code "38") (name "/MDIC_N") (class "Default")
      (node (ref "J4") (pin "5") (pinfunction "BI_DC-_5") (pintype "passive"))
      (node (ref "T1") (pin "20") (pinfunction "MX2+_20") (pintype "passive"))
    )
    (net (code "39") (name "/MDIC_P") (class "Default")
      (node (ref "J4") (pin "4") (pinfunction "BI_DC+_4") (pintype "passive"))
      (node (ref "T1") (pin "19") (pinfunction "MX2-_19") (pintype "passive"))
    )
    (net (code "40") (name "/MDID_N") (class "Default")
      (node (ref "J4") (pin "8") (pinfunction "BI_DD-_8") (pintype "passive"))
      (node (ref "T1") (pin "23") (pinfunction "MX1+_23") (pintype "passive"))
    )
    (net (code "41") (name "/MDID_P") (class "Default")
      (node (ref "J4") (pin "7") (pinfunction "BI_DD+_7") (pintype "passive"))
      (node (ref "T1") (pin "22") (pinfunction "MX1-_22") (pintype "passive"))
    )
    (net (code "42") (name "/MUX1_CTRL") (class "Default")
      (node (ref "R6") (pin "1") (pinfunction "1_1") (pintype "passive"))
      (node (ref "S1") (pin "3") (pinfunction "COM_1_3") (pintype "passive"))
      (node (ref "U2") (pin "6") (pinfunction "S_6") (pintype "passive"))
    )
    (net (code "43") (name "/MUX2_CTRL") (class "Default")
      (node (ref "R7") (pin "1") (pinfunction "1_1") (pintype "passive"))
      (node (ref "S1") (pin "4") (pinfunction "COM_2_4") (pintype "passive"))
      (node (ref "U4") (pin "6") (pinfunction "S_6") (pintype "passive"))
    )
    (net (code "44") (name "/RESET_N") (class "Default")
      (node (ref "R19") (pin "1") (pinfunction "1_1") (pintype "passive"))
      (node (ref "U5") (pin "23") (pinfunction "HW_RSTN_23") (pintype "passive"))
    )
    (net (code "45") (name "/RF") (class "Default")
      (node (ref "C7") (pin "2") (pinfunction "2_2") (pintype "passive"))
      (node (ref "IC1") (pin "11") (pinfunction "RF_IN_11") (pintype "passive"))
      (node (ref "IC2") (pin "11") (pinfunction "RF_IN_11") (pintype "passive"))
    )
    (net (code "46") (name "/SPI_CLK") (class "Default")
      (node (ref "R35") (pin "2") (pinfunction "2_2") (pintype "passive"))
      (node (ref "U5") (pin "51") (pinfunction "SPI_CLK_51") (pintype "passive"))
      (node (ref "U7") (pin "6") (pinfunction "SCK_6") (pintype "input"))
    )
    (net (code "47") (name "/SPI_CS") (class "Default")
      (node (ref "R36") (pin "2") (pinfunction "2_2") (pintype "passive"))
      (node (ref "U5") (pin "50") (pinfunction "SPI_CS0_50") (pintype "passive"))
      (node (ref "U7") (pin "1") (pinfunction "~{CE}_1") (pintype "input"))
    )
    (net (code "48") (name "/SPI_DIO") (class "Default")
      (node (ref "R34") (pin "2") (pinfunction "2_2") (pintype "passive"))
      (node (ref "R39") (pin "2") (pinfunction "2_2") (pintype "passive"))
      (node (ref "U5") (pin "52") (pinfunction "SPI_DIO_52") (pintype "passive"))
      (node (ref "U7") (pin "5") (pinfunction "SI_5") (pintype "input"))
    )
    (net (code "49") (name "/SSRX_N") (class "Default")
      (node (ref "D5") (pin "2") (pinfunction "D-_2") (pintype "passive"))
      (node (ref "J6") (pin "A10") (pinfunction "SSRXn2_A10") (pintype "passive"))
      (node (ref "J6") (pin "B10") (pinfunction "SSRXn1_B10") (pintype "passive"))
      (node (ref "U5") (pin "44") (pinfunction "SSUSBRXN_44") (pintype "passive"))
    )
    (net (code "50") (name "/SSRX_P") (class "Default")
      (node (ref "D5") (pin "1") (pinfunction "D+_1") (pintype "passive"))
      (node (ref "J6") (pin "A11") (pinfunction "SSRXp2_A11") (pintype "passive"))
      (node (ref "J6") (pin "B11") (pinfunction "SSRXp1_B11") (pintype "passive"))
      (node (ref "U5") (pin "45") (pinfunction "SSUSBRXP_45") (pintype "passive"))
    )
    (net (code "51") (name "/SSTX_N") (class "Default")
      (node (ref "C9") (pin "2") (pinfunction "2_2") (pintype "passive"))
      (node (ref "D3") (pin "2") (pinfunction "D-_2") (pintype "passive"))
      (node (ref "U5") (pin "41") (pinfunction "SSUSB_TXN_41") (pintype "passive"))
    )
    (net (code "52") (name "/SSTX_P") (class "Default")
      (node (ref "C8") (pin "2") (pinfunction "2_2") (pintype "passive"))
      (node (ref "D3") (pin "1") (pinfunction "D+_1") (pintype "passive"))
      (node (ref "U5") (pin "42") (pinfunction "SSUSB_TXP_42") (pintype "passive"))
    )
    (net (code "53") (name "/USB3.0_SSTX_N") (class "Default")
      (node (ref "C9") (pin "1") (pinfunction "1_1") (pintype "passive"))
      (node (ref "J6") (pin "A3") (pinfunction "SSTXn1_A3") (pintype "passive"))
      (node (ref "J6") (pin "B3") (pinfunction "SSTXn2_B3") (pintype "passive"))
    )
    (net (code "54") (name "/USB3.0_SSTX_P") (class "Default")
      (node (ref "C8") (pin "1") (pinfunction "1_1") (pintype "passive"))
      (node (ref "J6") (pin "A2") (pinfunction "SSTXp1_A2") (pintype "passive"))
      (node (ref "J6") (pin "B2") (pinfunction "SSTXp2_B2") (pintype "passive"))
    )
    (net (code "55") (name "/VBUS") (class "Default")
      (node (ref "R17") (pin "1") (pinfunction "1_1") (pintype "passive"))
      (node (ref "R18") (pin "2") (pinfunction "2_2") (pintype "passive"))
      (node (ref "U5") (pin "34") (pinfunction "GPIO9(VBUS)_34") (pintype "passive"))
    )
    (net (code "56") (name "/VCORE_LDO") (class "Default")
      (node (ref "C21") (pin "2") (pinfunction "2_2") (pintype "passive"))
      (node (ref "FB1") (pin "1") (pinfunction "1_1") (pintype "passive"))
      (node (ref "U5") (pin "55") (pinfunction "VCORE_LDO_55") (pintype "passive"))
    )
    (net (code "57") (name "/XTL20N") (class "Default")
      (node (ref "R27") (pin "2") (pinfunction "2_2") (pintype "passive"))
      (node (ref "U5") (pin "16") (pinfunction "XTAL_XO_16") (pintype "passive"))
    )
    (net (code "58") (name "/XTL20P") (class "Default")
      (node (ref "R26") (pin "2") (pinfunction "2_2") (pintype "passive"))
      (node (ref "U5") (pin "17") (pinfunction "XTAL_IN_17") (pintype "passive"))
    )
    (net (code "59") (name "DVDD_33") (class "Default")
      (node (ref "C18") (pin "2") (pinfunction "2_2") (pintype "passive"))
      (node (ref "C20") (pin "2") (pinfunction "2_2") (pintype "passive"))
      (node (ref "C31") (pin "2") (pinfunction "2_2") (pintype "passive"))
      (node (ref "C32") (pin "2") (pinfunction "2_2") (pintype "passive"))
      (node (ref "C33") (pin "2") (pinfunction "2_2") (pintype "passive"))
      (node (ref "C34") (pin "2") (pinfunction "2_2") (pintype "passive"))
      (node (ref "FB4") (pin "1") (pinfunction "1_1") (pintype "passive"))
      (node (ref "FB5") (pin "1") (pinfunction "1_1") (pintype "passive"))
      (node (ref "L2") (pin "2") (pinfunction "2_2") (pintype "passive"))
      (node (ref "R10") (pin "2") (pinfunction "2_2") (pintype "passive"))
      (node (ref "R19") (pin "2") (pinfunction "2_2") (pintype "passive"))
      (node (ref "R22") (pin "2") (pinfunction "2_2") (pintype "passive"))
      (node (ref "R24") (pin "2") (pinfunction "2_2") (pintype "passive"))
      (node (ref "R25") (pin "2") (pinfunction "2_2") (pintype "passive"))
      (node (ref "R31") (pin "1") (pinfunction "1_1") (pintype "passive"))
      (node (ref "R32") (pin "1") (pinfunction "1_1") (pintype "passive"))
      (node (ref "R34") (pin "1") (pinfunction "1_1") (pintype "passive"))
      (node (ref "R35") (pin "1") (pinfunction "1_1") (pintype "passive"))
      (node (ref "R36") (pin "1") (pinfunction "1_1") (pintype "passive"))
      (node (ref "R37") (pin "1") (pinfunction "1_1") (pintype "passive"))
      (node (ref "R38") (pin "1") (pinfunction "1_1") (pintype "passive"))
      (node (ref "R46") (pin "2") (pinfunction "2_2") (pintype "passive"))
      (node (ref "R47") (pin "2") (pinfunction "2_2") (pintype "passive"))
      (node (ref "R8") (pin "2") (pinfunction "2_2") (pintype "passive"))
      (node (ref "U5") (pin "25") (pinfunction "DVDD33_25") (pintype "passive"))
      (node (ref "U5") (pin "36") (pinfunction "DVDD33_36") (pintype "passive"))
      (node (ref "U5") (pin "54") (pinfunction "AVDD33_LDO_54") (pintype "passive"))
      (node (ref "U5") (pin "59") (pinfunction "AVD33_BUCK_59") (pintype "passive"))
      (node (ref "U6") (pin "1") (pinfunction "VO/VFB_1") (pintype "bidirectional"))
      (node (ref "U7") (pin "8") (pinfunction "VDD_8") (pintype "power_in"))
    )
    (net (code "60") (name "GND") (class "Default")
      (node (ref "C1") (pin "1") (pinfunction "1_1") (pintype "passive"))
      (node (ref "C10") (pin "1") (pinfunction "1_1") (pintype "passive"))
      (node (ref "C11") (pin "1") (pinfunction "1_1") (pintype "passive"))
      (node (ref "C12") (pin "1") (pinfunction "1_1") (pintype "passive"))
      (node (ref "C13") (pin "1") (pinfunction "1_1") (pintype "passive"))
      (node (ref "C14") (pin "1") (pinfunction "1_1") (pintype "passive"))
      (node (ref "C15") (pin "1") (pinfunction "1_1") (pintype "passive"))
      (node (ref "C16") (pin "1") (pinfunction "1_1") (pintype "passive"))
      (node (ref "C17") (pin "1") (pinfunction "1_1") (pintype "passive"))
      (node (ref "C18") (pin "1") (pinfunction "1_1") (pintype "passive"))
      (node (ref "C19") (pin "1") (pinfunction "1_1") (pintype "passive"))
      (node (ref "C2") (pin "1") (pinfunction "1_1") (pintype "passive"))
      (node (ref "C20") (pin "1") (pinfunction "1_1") (pintype "passive"))
      (node (ref "C21") (pin "1") (pinfunction "1_1") (pintype "passive"))
      (node (ref "C22") (pin "1") (pinfunction "1_1") (pintype "passive"))
      (node (ref "C23") (pin "1") (pinfunction "1_1") (pintype "passive"))
      (node (ref "C24") (pin "1") (pinfunction "1_1") (pintype "passive"))
      (node (ref "C25") (pin "1") (pinfunction "1_1") (pintype "passive"))
      (node (ref "C26") (pin "1") (pinfunction "1_1") (pintype "passive"))
      (node (ref "C27") (pin "1") (pinfunction "1_1") (pintype "passive"))
      (node (ref "C28") (pin "1") (pinfunction "1_1") (pintype "passive"))
      (node (ref "C29") (pin "1") (pinfunction "1_1") (pintype "passive"))
      (node (ref "C3") (pin "1") (pinfunction "1_1") (pintype "passive"))
      (node (ref "C30") (pin "1") (pinfunction "1_1") (pintype "passive"))
      (node (ref "C31") (pin "1") (pinfunction "1_1") (pintype "passive"))
      (node (ref "C32") (pin "1") (pinfunction "1_1") (pintype "passive"))
      (node (ref "C33") (pin "1") (pinfunction "1_1") (pintype "passive"))
      (node (ref "C34") (pin "1") (pinfunction "1_1") (pintype "passive"))
      (node (ref "C35") (pin "1") (pinfunction "1_1") (pintype "passive"))
      (node (ref "C36") (pin "1") (pinfunction "1_1") (pintype "passive"))
      (node (ref "C37") (pin "1") (pinfunction "1_1") (pintype "passive"))
      (node (ref "C38") (pin "1") (pinfunction "1_1") (pintype "passive"))
      (node (ref "C39") (pin "1") (pinfunction "1_1") (pintype "passive"))
      (node (ref "C4") (pin "1") (pinfunction "1_1") (pintype "passive"))
      (node (ref "C40") (pin "1") (pinfunction "1_1") (pintype "passive"))
      (node (ref "C41") (pin "1") (pinfunction "1_1") (pintype "passive"))
      (node (ref "C42") (pin "1") (pinfunction "1_1") (pintype "passive"))
      (node (ref "C43") (pin "1") (pinfunction "1_1") (pintype "passive"))
      (node (ref "C44") (pin "1") (pinfunction "1_1") (pintype "passive"))
      (node (ref "C45") (pin "2") (pinfunction "2_2") (pintype "passive"))
      (node (ref "C46") (pin "2") (pinfunction "2_2") (pintype "passive"))
      (node (ref "C48") (pin "2") (pinfunction "2_2") (pintype "passive"))
      (node (ref "C49") (pin "2") (pinfunction "2_2") (pintype "passive"))
      (node (ref "C5") (pin "1") (pinfunction "1_1") (pintype "passive"))
      (node (ref "C50") (pin "2") (pinfunction "2_2") (pintype "passive"))
      (node (ref "C51") (pin "2") (pinfunction "2_2") (pintype "passive"))
      (node (ref "C6") (pin "2") (pinfunction "2_2") (pintype "passive"))
      (node (ref "D3") (pin "3") (pinfunction "GND_3") (pintype "passive"))
      (node (ref "D4") (pin "3") (pinfunction "GND_3") (pintype "passive"))
      (node (ref "D5") (pin "3") (pinfunction "GND_3") (pintype "passive"))
      (node (ref "IC1") (pin "10") (pinfunction "GND_1_10") (pintype "passive"))
      (node (ref "IC1") (pin "12") (pinfunction "GND_2_12") (pintype "passive"))
      (node (ref "IC1") (pin "13") (pinfunction "GND_3_13") (pintype "passive"))
      (node (ref "IC1") (pin "24") (pinfunction "GND_4_24") (pintype "passive"))
      (node (ref "IC1") (pin "7") (pinfunction "V_USB_7") (pintype "passive"))
      (node (ref "IC2") (pin "1") (pinfunction "GND_1_1") (pintype "passive"))
      (node (ref "IC2") (pin "10") (pinfunction "GND_2_10") (pintype "passive"))
      (node (ref "IC2") (pin "12") (pinfunction "GND_3_12") (pintype "passive"))
      (node (ref "J1") (pin "2") (pinfunction "2_2") (pintype "passive"))
      (node (ref "J1") (pin "3") (pinfunction "3_3") (pintype "passive"))
      (node (ref "J1") (pin "4") (pinfunction "4_4") (pintype "passive"))
      (node (ref "J1") (pin "5") (pinfunction "5_5") (pintype "passive"))
      (node (ref "J2") (pin "2") (pinfunction "2_2") (pintype "passive"))
      (node (ref "J2") (pin "3") (pinfunction "3_3") (pintype "passive"))
      (node (ref "J2") (pin "4") (pinfunction "4_4") (pintype "passive"))
      (node (ref "J2") (pin "5") (pinfunction "5_5") (pintype "passive"))
      (node (ref "J3") (pin "1") (pinfunction "1_1") (pintype "passive"))
      (node (ref "J5") (pin "2") (pinfunction "2_2") (pintype "passive"))
      (node (ref "J5") (pin "3") (pinfunction "3_3") (pintype "passive"))
      (node (ref "J5") (pin "4") (pinfunction "4_4") (pintype "passive"))
      (node (ref "J5") (pin "5") (pinfunction "5_5") (pintype "passive"))
      (node (ref "J6") (pin "A1") (pinfunction "GND_A1") (pintype "passive"))
      (node (ref "J6") (pin "A12") (pinfunction "GND_A12") (pintype "passive"))
      (node (ref "J6") (pin "B1") (pinfunction "GND_B1") (pintype "passive"))
      (node (ref "J6") (pin "B12") (pinfunction "GND_B12") (pintype "passive"))
      (node (ref "R1") (pin "2") (pinfunction "2_2") (pintype "passive"))
      (node (ref "R15") (pin "2") (pinfunction "2_2") (pintype "passive"))
      (node (ref "R16") (pin "2") (pinfunction "2_2") (pintype "passive"))
      (node (ref "R18") (pin "1") (pinfunction "1_1") (pintype "passive"))
      (node (ref "R21") (pin "1") (pinfunction "1_1") (pintype "passive"))
      (node (ref "R29") (pin "2") (pinfunction "2_2") (pintype "passive"))
      (node (ref "R30") (pin "2") (pinfunction "2_2") (pintype "passive"))
      (node (ref "R33") (pin "1") (pinfunction "1_1") (pintype "passive"))
      (node (ref "R4") (pin "1") (pinfunction "1_1") (pintype "passive"))
      (node (ref "R41") (pin "2") (pinfunction "2_2") (pintype "passive"))
      (node (ref "S1") (pin "1") (pinfunction "NO_1_1") (pintype "passive"))
      (node (ref "S1") (pin "2") (pinfunction "NO_2_2") (pintype "passive"))
      (node (ref "U1") (pin "4") (pinfunction "GND_4") (pintype "passive"))
      (node (ref "U2") (pin "2") (pinfunction "GND_2") (pintype "passive"))
      (node (ref "U3") (pin "4") (pinfunction "GND_4") (pintype "passive"))
      (node (ref "U4") (pin "2") (pinfunction "GND_2") (pintype "passive"))
      (node (ref "U5") (pin "1") (pinfunction "AVSS33_BUCK_1") (pintype "passive"))
      (node (ref "U5") (pin "2") (pinfunction "AVSS33_BUCK_2") (pintype "passive"))
      (node (ref "U5") (pin "61") (pinfunction "E_PAD_61") (pintype "passive"))
      (node (ref "U6") (pin "2") (pinfunction "GND_2") (pintype "power_in"))
      (node (ref "U6") (pin "7") (pinfunction "Thermal_Pad_7") (pintype "power_in"))
      (node (ref "U7") (pin "4") (pinfunction "VSS_4") (pintype "power_in"))
      (node (ref "U7") (pin "9") (pinfunction "VSS_9") (pintype "power_in"))
      (node (ref "U8") (pin "2") (pinfunction "GND_2") (pintype "power_in"))
      (node (ref "U8") (pin "7") (pinfunction "Thermal_Pad_7") (pintype "power_in"))
      (node (ref "Y1") (pin "2") (pinfunction "GND_2") (pintype "passive"))
      (node (ref "Y1") (pin "4") (pinfunction "GND_4") (pintype "passive"))
    )
    (net (code "61") (name "Net-(C5-Pad2)") (class "Default")
      (node (ref "C5") (pin "2") (pinfunction "2_2") (pintype "passive"))
      (node (ref "L1") (pin "1") (pinfunction "1_1") (pintype "passive"))
      (node (ref "R12") (pin "2") (pinfunction "2_2") (pintype "passive"))
    )
    (net (code "62") (name "Net-(C13-Pad2)") (class "Default")
      (node (ref "C13") (pin "2") (pinfunction "2_2") (pintype "passive"))
      (node (ref "R26") (pin "1") (pinfunction "1_1") (pintype "passive"))
      (node (ref "Y1") (pin "1") (pinfunction "1_1") (pintype "passive"))
    )
    (net (code "63") (name "Net-(C14-Pad2)") (class "Default")
      (node (ref "C14") (pin "2") (pinfunction "2_2") (pintype "passive"))
      (node (ref "R27") (pin "1") (pinfunction "1_1") (pintype "passive"))
      (node (ref "Y1") (pin "3") (pinfunction "3_3") (pintype "passive"))
    )
    (net (code "64") (name "Net-(C47-Pad2)") (class "Default")
      (node (ref "C47") (pin "2") (pinfunction "2_2") (pintype "passive"))
      (node (ref "R20") (pin "2") (pinfunction "2_2") (pintype "passive"))
      (node (ref "R42") (pin "2") (pinfunction "2_2") (pintype "passive"))
      (node (ref "R43") (pin "2") (pinfunction "2_2") (pintype "passive"))
      (node (ref "R44") (pin "2") (pinfunction "2_2") (pintype "passive"))
      (node (ref "R45") (pin "2") (pinfunction "2_2") (pintype "passive"))
    )
    (net (code "65") (name "Net-(D1-PadA)") (class "Default")
      (node (ref "D1") (pin "A") (pinfunction "A_A") (pintype "passive"))
      (node (ref "R2") (pin "1") (pinfunction "1_1") (pintype "passive"))
    )
    (net (code "66") (name "Net-(D2-PadA)") (class "Default")
      (node (ref "D2") (pin "A") (pinfunction "A_A") (pintype "passive"))
      (node (ref "R5") (pin "1") (pinfunction "1_1") (pintype "passive"))
    )
    (net (code "67") (name "Net-(D6-Pad1)") (class "Default")
      (node (ref "D6") (pin "1") (pinfunction "1_1") (pintype "passive"))
      (node (ref "R46") (pin "1") (pinfunction "1_1") (pintype "passive"))
    )
    (net (code "68") (name "Net-(D7-Pad1)") (class "Default")
      (node (ref "D7") (pin "1") (pinfunction "1_1") (pintype "passive"))
      (node (ref "R47") (pin "1") (pinfunction "1_1") (pintype "passive"))
    )
    (net (code "69") (name "Net-(J4-A_GR)") (class "Default")
      (node (ref "J4") (pin "11") (pinfunction "A_GR_11") (pintype "passive"))
      (node (ref "R10") (pin "1") (pinfunction "1_1") (pintype "passive"))
    )
    (net (code "70") (name "Net-(J4-A_YEL)") (class "Default")
      (node (ref "J4") (pin "9") (pinfunction "A_YEL_9") (pintype "passive"))
      (node (ref "R8") (pin "1") (pinfunction "1_1") (pintype "passive"))
    )
    (net (code "71") (name "Net-(J6-CC1)") (class "Default")
      (node (ref "J6") (pin "A5") (pinfunction "CC1_A5") (pintype "passive"))
      (node (ref "R29") (pin "1") (pinfunction "1_1") (pintype "passive"))
    )
    (net (code "72") (name "Net-(J6-CC2)") (class "Default")
      (node (ref "J6") (pin "B5") (pinfunction "CC2_B5") (pintype "passive"))
      (node (ref "R30") (pin "1") (pinfunction "1_1") (pintype "passive"))
    )
    (net (code "73") (name "Net-(J6-Shield)") (class "Default")
      (node (ref "C15") (pin "2") (pinfunction "2_2") (pintype "passive"))
      (node (ref "J6") (pin "S") (pinfunction "Shield_S") (pintype "passive"))
      (node (ref "R33") (pin "2") (pinfunction "2_2") (pintype "passive"))
    )
    (net (code "74") (name "Net-(Q1-G)") (class "Default")
      (node (ref "Q1") (pin "1") (pinfunction "G_1") (pintype "passive"))
      (node (ref "R13") (pin "1") (pinfunction "1_1") (pintype "passive"))
      (node (ref "R14") (pin "2") (pinfunction "2_2") (pintype "passive"))
      (node (ref "R16") (pin "1") (pinfunction "1_1") (pintype "passive"))
    )
    (net (code "75") (name "Net-(Q1-S)") (class "Default")
      (node (ref "Q1") (pin "2") (pinfunction "S_2") (pintype "passive"))
      (node (ref "R12") (pin "1") (pinfunction "1_1") (pintype "passive"))
    )
    (net (code "76") (name "Net-(T1-MCT1)") (class "Default")
      (node (ref "R20") (pin "1") (pinfunction "1_1") (pintype "passive"))
      (node (ref "T1") (pin "24") (pinfunction "MCT1_24") (pintype "passive"))
    )
    (net (code "77") (name "Net-(T1-MCT2)") (class "Default")
      (node (ref "R42") (pin "1") (pinfunction "1_1") (pintype "passive"))
      (node (ref "T1") (pin "21") (pinfunction "MCT2_21") (pintype "passive"))
    )
    (net (code "78") (name "Net-(T1-MCT3)") (class "Default")
      (node (ref "R43") (pin "1") (pinfunction "1_1") (pintype "passive"))
      (node (ref "T1") (pin "18") (pinfunction "MCT3_18") (pintype "passive"))
    )
    (net (code "79") (name "Net-(T1-MCT4)") (class "Default")
      (node (ref "R44") (pin "1") (pinfunction "1_1") (pintype "passive"))
      (node (ref "T1") (pin "15") (pinfunction "MCT4_15") (pintype "passive"))
    )
    (net (code "80") (name "Net-(T1-TCT1)") (class "Default")
      (node (ref "C48") (pin "1") (pinfunction "1_1") (pintype "passive"))
      (node (ref "T1") (pin "1") (pinfunction "TCT1_1") (pintype "passive"))
    )
    (net (code "81") (name "Net-(T1-TCT2)") (class "Default")
      (node (ref "C49") (pin "1") (pinfunction "1_1") (pintype "passive"))
      (node (ref "T1") (pin "4") (pinfunction "TCT2_4") (pintype "passive"))
    )
    (net (code "82") (name "Net-(T1-TCT3)") (class "Default")
      (node (ref "C50") (pin "1") (pinfunction "1_1") (pintype "passive"))
      (node (ref "T1") (pin "7") (pinfunction "TCT3_7") (pintype "passive"))
    )
    (net (code "83") (name "Net-(T1-TCT4)") (class "Default")
      (node (ref "C51") (pin "1") (pinfunction "1_1") (pintype "passive"))
      (node (ref "T1") (pin "10") (pinfunction "TCT4_10") (pintype "passive"))
    )
    (net (code "84") (name "Net-(U1-~{OE1})") (class "Default")
      (node (ref "R1") (pin "1") (pinfunction "1_1") (pintype "passive"))
      (node (ref "U1") (pin "1") (pinfunction "~{OE1}_1") (pintype "passive"))
      (node (ref "U1") (pin "7") (pinfunction "~{OE2}_7") (pintype "passive"))
    )
    (net (code "85") (name "Net-(U3-~{OE1})") (class "Default")
      (node (ref "R4") (pin "2") (pinfunction "2_2") (pintype "passive"))
      (node (ref "U3") (pin "1") (pinfunction "~{OE1}_1") (pintype "passive"))
      (node (ref "U3") (pin "7") (pinfunction "~{OE2}_7") (pintype "passive"))
    )
    (net (code "86") (name "Net-(U4-B2)") (class "Default")
      (node (ref "J2") (pin "1") (pinfunction "1_1") (pintype "passive"))
      (node (ref "U4") (pin "1") (pinfunction "B2_1") (pintype "passive"))
    )
    (net (code "87") (name "Net-(U5-AVDD18_XTAL)") (class "Default")
      (node (ref "C28") (pin "2") (pinfunction "2_2") (pintype "passive"))
      (node (ref "C29") (pin "2") (pinfunction "2_2") (pintype "passive"))
      (node (ref "FB3") (pin "1") (pinfunction "1_1") (pintype "passive"))
      (node (ref "U5") (pin "15") (pinfunction "AVDD18_XTAL_15") (pintype "passive"))
    )
    (net (code "88") (name "Net-(U5-GPIO10(SYNCE_LOCK))") (class "Default")
      (node (ref "R24") (pin "1") (pinfunction "1_1") (pintype "passive"))
      (node (ref "U5") (pin "19") (pinfunction "GPIO10(SYNCE_LOCK)_19") (pintype "passive"))
    )
    (net (code "89") (name "Net-(U5-MPXP)") (class "Default")
      (node (ref "R21") (pin "2") (pinfunction "2_2") (pintype "passive"))
      (node (ref "U5") (pin "9") (pinfunction "MPXP_9") (pintype "passive"))
    )
    (net (code "90") (name "Net-(U6-SW)") (class "Default")
      (node (ref "L2") (pin "1") (pinfunction "1_1") (pintype "passive"))
      (node (ref "U6") (pin "3") (pinfunction "SW_3") (pintype "passive"))
    )
    (net (code "91") (name "Net-(U7-SO)") (class "Default")
      (node (ref "R39") (pin "1") (pinfunction "1_1") (pintype "passive"))
      (node (ref "U7") (pin "2") (pinfunction "SO_2") (pintype "output"))
    )
    (net (code "92") (name "Net-(U7-~{HOLD})") (class "Default")
      (node (ref "R37") (pin "2") (pinfunction "2_2") (pintype "passive"))
      (node (ref "U7") (pin "7") (pinfunction "~{HOLD}_7") (pintype "input"))
    )
    (net (code "93") (name "Net-(U7-~{WP})") (class "Default")
      (node (ref "R38") (pin "2") (pinfunction "2_2") (pintype "passive"))
      (node (ref "U7") (pin "3") (pinfunction "~{WP}_3") (pintype "input"))
    )
    (net (code "94") (name "Net-(U8-SW)") (class "Default")
      (node (ref "L3") (pin "1") (pinfunction "1_1") (pintype "passive"))
      (node (ref "U8") (pin "3") (pinfunction "SW_3") (pintype "passive"))
    )
    (net (code "95") (name "Net-(U8-VO{slash}VFB)") (class "Default")
      (node (ref "R40") (pin "2") (pinfunction "2_2") (pintype "passive"))
      (node (ref "R41") (pin "1") (pinfunction "1_1") (pintype "passive"))
      (node (ref "U8") (pin "1") (pinfunction "VO/VFB_1") (pintype "bidirectional"))
    )
    (net (code "96") (name "PE") (class "Default")
      (node (ref "C45") (pin "1") (pinfunction "1_1") (pintype "passive"))
      (node (ref "C46") (pin "1") (pinfunction "1_1") (pintype "passive"))
      (node (ref "C47") (pin "1") (pinfunction "1_1") (pintype "passive"))
      (node (ref "C6") (pin "1") (pinfunction "1_1") (pintype "passive"))
      (node (ref "J4") (pin "MH1") (pinfunction "MH1_MH1") (pintype "passive"))
      (node (ref "J4") (pin "MH2") (pinfunction "MH2_MH2") (pintype "passive"))
      (node (ref "R15") (pin "1") (pinfunction "1_1") (pintype "passive"))
      (node (ref "R45") (pin "1") (pinfunction "1_1") (pintype "passive"))
    )
    (net (code "97") (name "VBUS_+5V") (class "Default")
      (node (ref "C1") (pin "2") (pinfunction "2_2") (pintype "passive"))
      (node (ref "C19") (pin "2") (pinfunction "2_2") (pintype "passive"))
      (node (ref "C2") (pin "2") (pinfunction "2_2") (pintype "passive"))
      (node (ref "C3") (pin "2") (pinfunction "2_2") (pintype "passive"))
      (node (ref "C4") (pin "2") (pinfunction "2_2") (pintype "passive"))
      (node (ref "C40") (pin "2") (pinfunction "2_2") (pintype "passive"))
      (node (ref "J3") (pin "2") (pinfunction "2_2") (pintype "passive"))
      (node (ref "J6") (pin "A4") (pinfunction "VBUS_A4") (pintype "passive"))
      (node (ref "J6") (pin "A9") (pinfunction "VBUS_A9") (pintype "passive"))
      (node (ref "J6") (pin "B4") (pinfunction "VBUS_B4") (pintype "passive"))
      (node (ref "J6") (pin "B9") (pinfunction "VBUS_B9") (pintype "passive"))
      (node (ref "R11") (pin "2") (pinfunction "2_2") (pintype "passive"))
      (node (ref "R17") (pin "2") (pinfunction "2_2") (pintype "passive"))
      (node (ref "R2") (pin "2") (pinfunction "2_2") (pintype "passive"))
      (node (ref "R5") (pin "2") (pinfunction "2_2") (pintype "passive"))
      (node (ref "R6") (pin "2") (pinfunction "2_2") (pintype "passive"))
      (node (ref "R7") (pin "2") (pinfunction "2_2") (pintype "passive"))
      (node (ref "U1") (pin "8") (pinfunction "VCC_8") (pintype "passive"))
      (node (ref "U2") (pin "5") (pinfunction "VCC_5") (pintype "passive"))
      (node (ref "U3") (pin "8") (pinfunction "VCC_8") (pintype "passive"))
      (node (ref "U4") (pin "5") (pinfunction "VCC_5") (pintype "passive"))
      (node (ref "U6") (pin "4") (pinfunction "VIN_SW_4") (pintype "input"))
      (node (ref "U6") (pin "5") (pinfunction "VIN_A_5") (pintype "input"))
      (node (ref "U6") (pin "6") (pinfunction "VINH_6") (pintype "input"))
      (node (ref "U8") (pin "4") (pinfunction "VIN_SW_4") (pintype "input"))
      (node (ref "U8") (pin "5") (pinfunction "VIN_A_5") (pintype "input"))
      (node (ref "U8") (pin "6") (pinfunction "VINH_6") (pintype "input"))
    )
    (net (code "98") (name "VCCK10") (class "Default")
      (node (ref "C30") (pin "2") (pinfunction "2_2") (pintype "passive"))
      (node (ref "C41") (pin "2") (pinfunction "2_2") (pintype "passive"))
      (node (ref "C42") (pin "2") (pinfunction "2_2") (pintype "passive"))
      (node (ref "C43") (pin "2") (pinfunction "2_2") (pintype "passive"))
      (node (ref "C44") (pin "2") (pinfunction "2_2") (pintype "passive"))
      (node (ref "L3") (pin "2") (pinfunction "2_2") (pintype "passive"))
      (node (ref "R40") (pin "1") (pinfunction "1_1") (pintype "passive"))
      (node (ref "U5") (pin "24") (pinfunction "VCCK_24") (pintype "passive"))
      (node (ref "U5") (pin "30") (pinfunction "VCCK_30") (pintype "passive"))
      (node (ref "U5") (pin "31") (pinfunction "VCCK_31") (pintype "passive"))
      (node (ref "U5") (pin "32") (pinfunction "VCCK_32") (pintype "passive"))
      (node (ref "U5") (pin "57") (pinfunction "VCCK_57") (pintype "passive"))
      (node (ref "U5") (pin "58") (pinfunction "VCCK_58") (pintype "passive"))
    )
    (net (code "99") (name "VDD_NEO") (class "Default")
      (node (ref "C10") (pin "2") (pinfunction "2_2") (pintype "passive"))
      (node (ref "C11") (pin "2") (pinfunction "2_2") (pintype "passive"))
      (node (ref "C12") (pin "2") (pinfunction "2_2") (pintype "passive"))
      (node (ref "FB5") (pin "2") (pinfunction "2_2") (pintype "passive"))
      (node (ref "IC1") (pin "2") (pinfunction "D_SEL_2") (pintype "passive"))
      (node (ref "IC1") (pin "22") (pinfunction "V_BCKP_22") (pintype "passive"))
      (node (ref "IC1") (pin "23") (pinfunction "VCC_23") (pintype "passive"))
      (node (ref "IC2") (pin "6") (pinfunction "V_BCKP_6") (pintype "passive"))
      (node (ref "IC2") (pin "8") (pinfunction "VCC_8") (pintype "passive"))
    )
    (net (code "100") (name "unconnected-(IC1-EXTINT-Pad4)") (class "Default")
      (node (ref "IC1") (pin "4") (pinfunction "EXTINT_4") (pintype "passive+no_connect"))
    )
    (net (code "101") (name "unconnected-(IC1-RESERVED_1-Pad15)") (class "Default")
      (node (ref "IC1") (pin "15") (pinfunction "RESERVED_1_15") (pintype "passive+no_connect"))
    )
    (net (code "102") (name "unconnected-(IC1-RESERVED_2-Pad16)") (class "Default")
      (node (ref "IC1") (pin "16") (pinfunction "RESERVED_2_16") (pintype "passive+no_connect"))
    )
    (net (code "103") (name "unconnected-(IC1-RESERVED_3-Pad17)") (class "Default")
      (node (ref "IC1") (pin "17") (pinfunction "RESERVED_3_17") (pintype "passive+no_connect"))
    )
    (net (code "104") (name "unconnected-(IC1-RESET_N-Pad8)") (class "Default")
      (node (ref "IC1") (pin "8") (pinfunction "RESET_N_8") (pintype "passive+no_connect"))
    )
    (net (code "105") (name "unconnected-(IC1-SAFEBOOT_N-Pad1)") (class "Default")
      (node (ref "IC1") (pin "1") (pinfunction "SAFEBOOT_N_1") (pintype "passive+no_connect"))
    )
    (net (code "106") (name "unconnected-(IC1-SCL_{slash}_SPI_SLK_-Pad19)") (class "Default")
      (node (ref "IC1") (pin "19") (pinfunction "SCL_/_SPI_SLK__19") (pintype "passive"))
    )
    (net (code "107") (name "unconnected-(IC1-SDA_{slash}_SPI_CS_N-Pad18)") (class "Default")
      (node (ref "IC1") (pin "18") (pinfunction "SDA_/_SPI_CS_N_18") (pintype "passive"))
    )
    (net (code "108") (name "unconnected-(IC1-USB_DM-Pad5)") (class "Default")
      (node (ref "IC1") (pin "5") (pinfunction "USB_DM_5") (pintype "passive+no_connect"))
    )
    (net (code "109") (name "unconnected-(IC1-USB_DP-Pad6)") (class "Default")
      (node (ref "IC1") (pin "6") (pinfunction "USB_DP_6") (pintype "passive+no_connect"))
    )
    (net (code "110") (name "unconnected-(IC1-VCC_RF-Pad9)") (class "Default")
      (node (ref "IC1") (pin "9") (pinfunction "VCC_RF_9") (pintype "passive+no_connect"))
    )
    (net (code "111") (name "unconnected-(IC2-EXTINT-Pad5)") (class "Default")
      (node (ref "IC2") (pin "5") (pinfunction "EXTINT_5") (pintype "passive+no_connect"))
    )
    (net (code "112") (name "unconnected-(IC2-RESET_N-Pad9)") (class "Default")
      (node (ref "IC2") (pin "9") (pinfunction "RESET_N_9") (pintype "passive+no_connect"))
    )
    (net (code "113") (name "unconnected-(IC2-SAFEBOOT_N-Pad18)") (class "Default")
      (node (ref "IC2") (pin "18") (pinfunction "SAFEBOOT_N_18") (pintype "passive+no_connect"))
    )
    (net (code "114") (name "unconnected-(IC2-SCL-Pad17)") (class "Default")
      (node (ref "IC2") (pin "17") (pinfunction "SCL_17") (pintype "passive+no_connect"))
    )
    (net (code "115") (name "unconnected-(IC2-SDA-Pad16)") (class "Default")
      (node (ref "IC2") (pin "16") (pinfunction "SDA_16") (pintype "passive+no_connect"))
    )
    (net (code "116") (name "unconnected-(IC2-VCC_RF-Pad14)") (class "Default")
      (node (ref "IC2") (pin "14") (pinfunction "VCC_RF_14") (pintype "passive+no_connect"))
    )
    (net (code "117") (name "unconnected-(IC2-VIO_SEL-Pad15)") (class "Default")
      (node (ref "IC2") (pin "15") (pinfunction "VIO_SEL_15") (pintype "passive"))
    )
    (net (code "118") (name "unconnected-(IC2-V_IO-Pad7)") (class "Default")
      (node (ref "IC2") (pin "7") (pinfunction "V_IO_7") (pintype "passive"))
    )
    (net (code "119") (name "unconnected-(J6-SBU1-PadA8)") (class "Default")
      (node (ref "J6") (pin "A8") (pinfunction "SBU1_A8") (pintype "passive+no_connect"))
    )
    (net (code "120") (name "unconnected-(J6-SBU2-PadB8)") (class "Default")
      (node (ref "J6") (pin "B8") (pinfunction "SBU2_B8") (pintype "passive+no_connect"))
    )
    (net (code "121") (name "unconnected-(U5-CKO-Pad18)") (class "Default")
      (node (ref "U5") (pin "18") (pinfunction "CKO_18") (pintype "passive+no_connect"))
    )
    (net (code "122") (name "unconnected-(U5-GPIO0(MDC)-Pad48)") (class "Default")
      (node (ref "U5") (pin "48") (pinfunction "GPIO0(MDC)_48") (pintype "passive+no_connect"))
    )
    (net (code "123") (name "unconnected-(U5-GPIO1(MDIO)-Pad49)") (class "Default")
      (node (ref "U5") (pin "49") (pinfunction "GPIO1(MDIO)_49") (pintype "passive+no_connect"))
    )
    (net (code "124") (name "unconnected-(U5-GPIO2-Pad22)") (class "Default")
      (node (ref "U5") (pin "22") (pinfunction "GPIO2_22") (pintype "passive+no_connect"))
    )
    (net (code "125") (name "unconnected-(U5-GPIO15(1588_TOD)-Pad47)") (class "Default")
      (node (ref "U5") (pin "47") (pinfunction "GPIO15(1588_TOD)_47") (pintype "passive+no_connect"))
    )
    (net (code "126") (name "unconnected-(U5-LX-Pad60)") (class "Default")
      (node (ref "U5") (pin "60") (pinfunction "LX_60") (pintype "passive+no_connect"))
    )
  )
)
